# TI.net
KiCad netlist of a schematic drawn in EasyEDA Pro
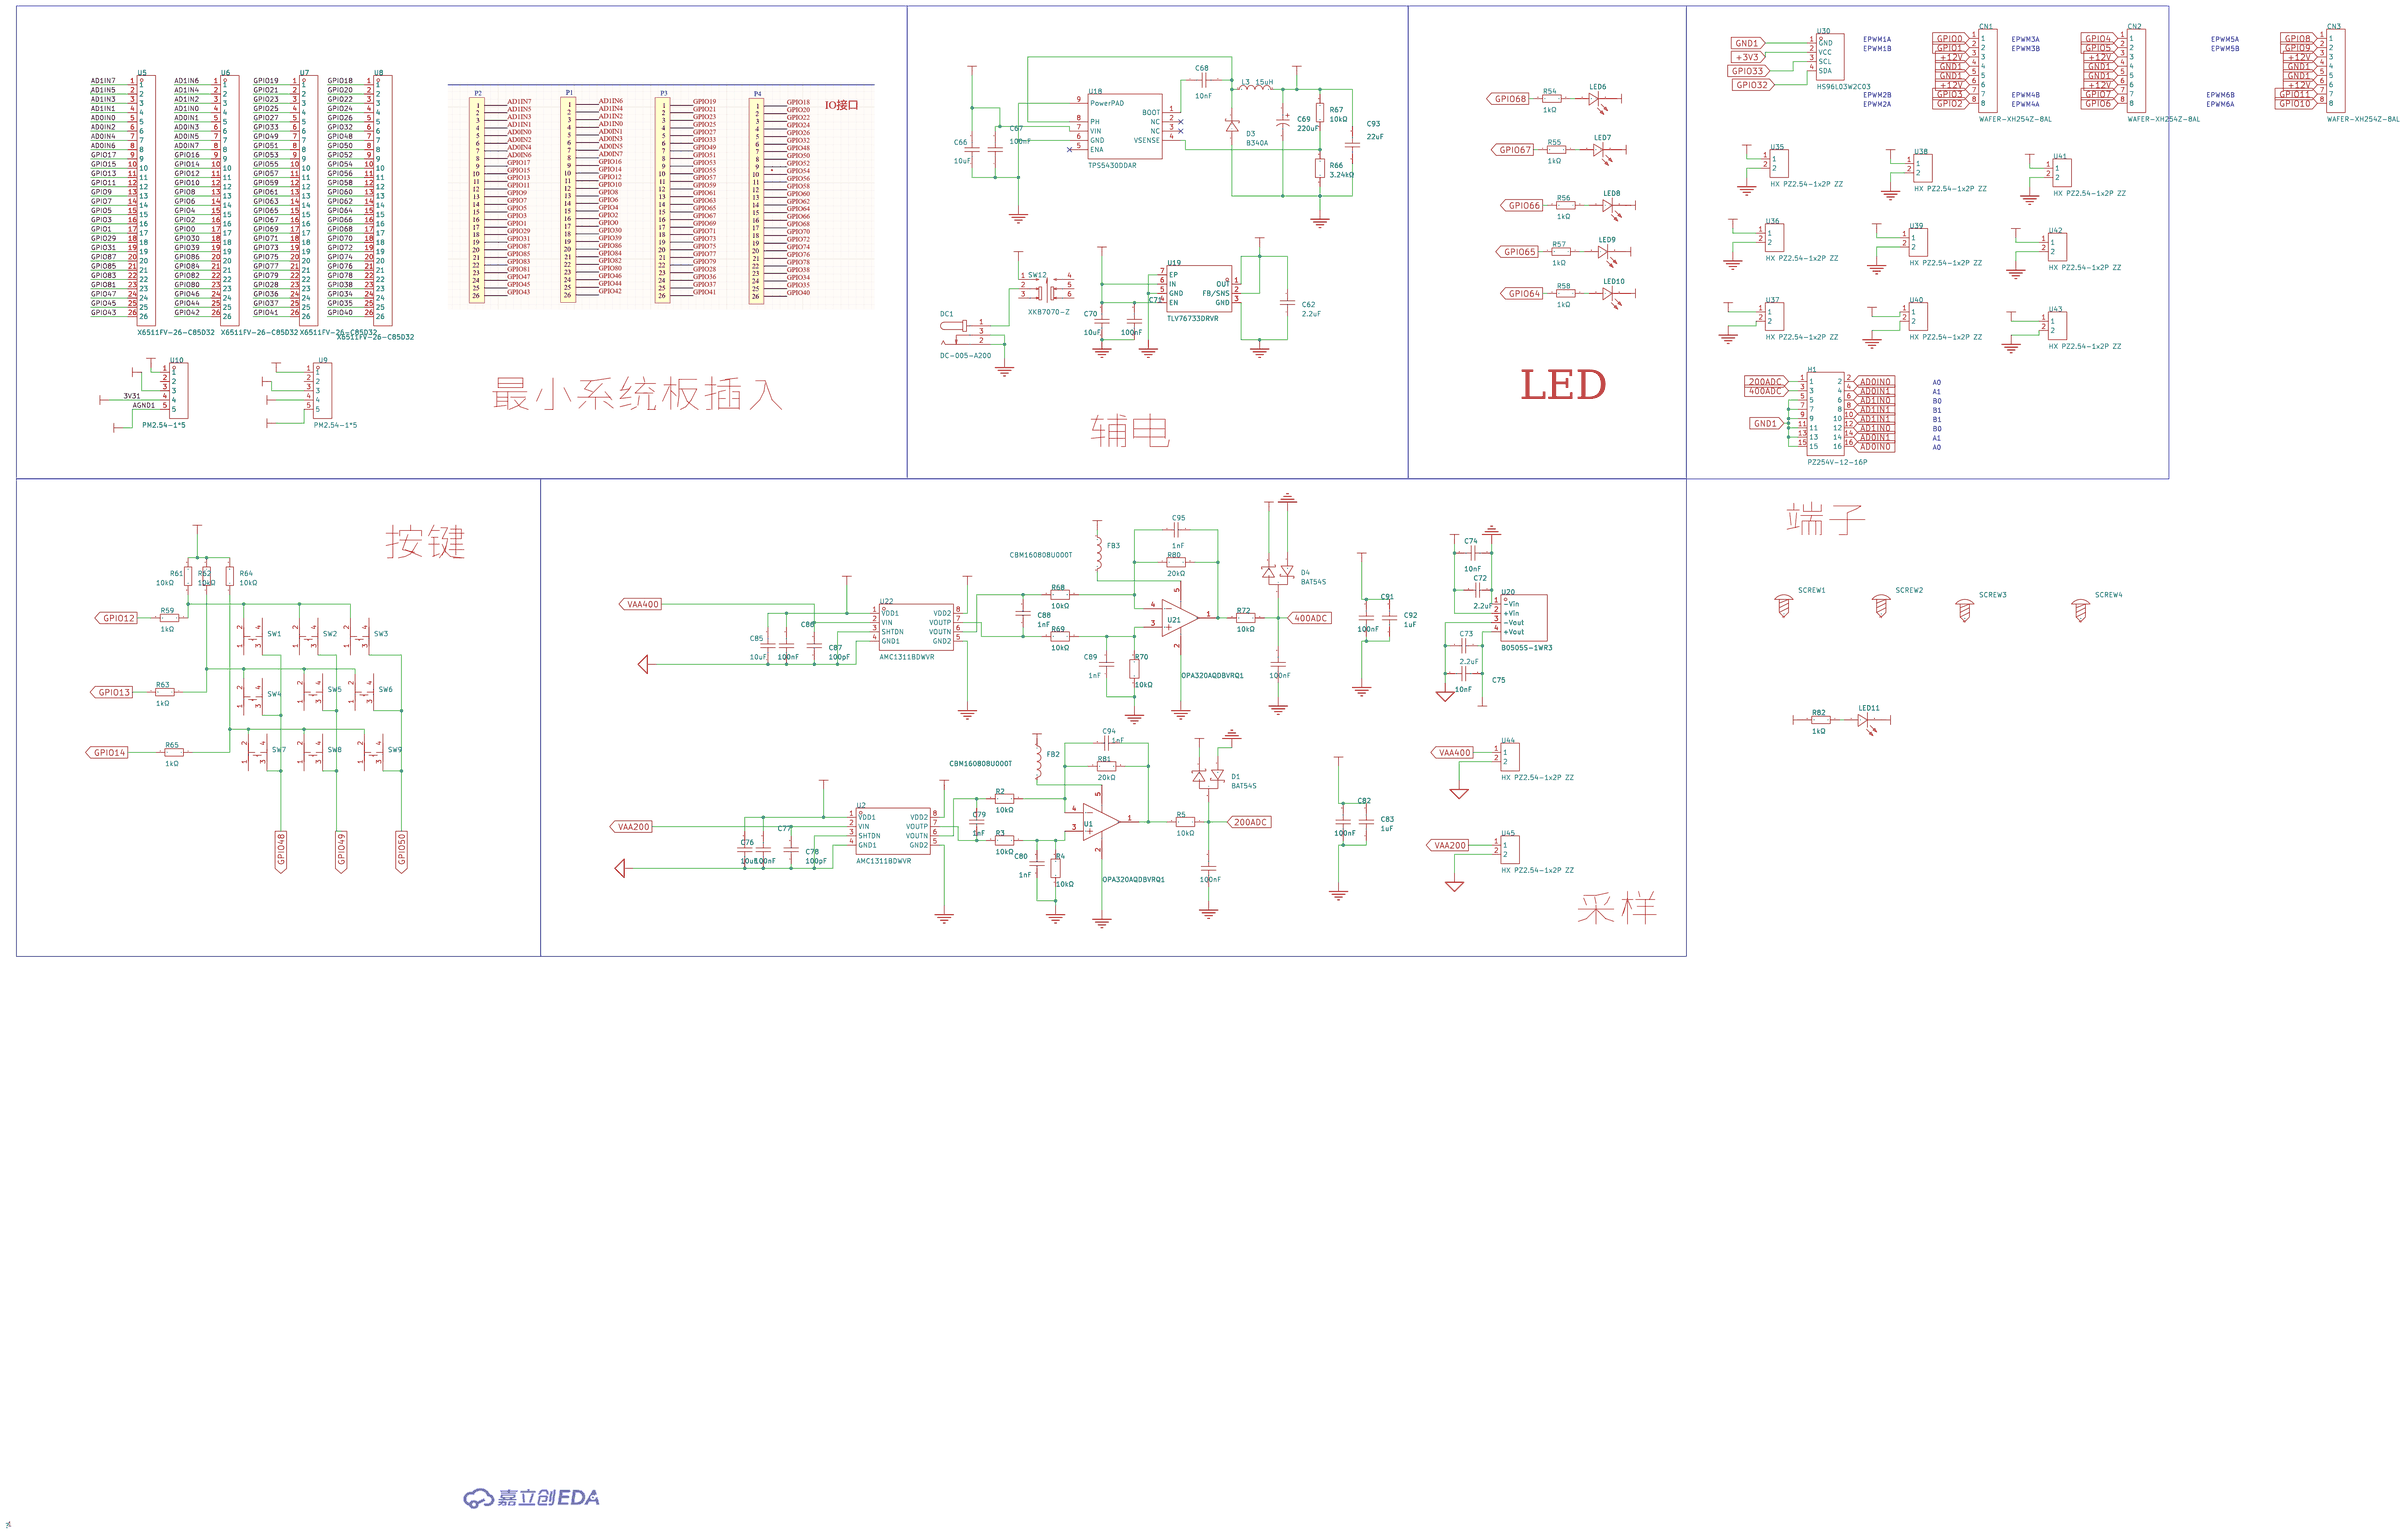
[diagram p0: schematic sheet]

(export (version "E")
  (design (tool "Eeschema 10.0.6"))
  (components
    (comp (ref "C62")
      (value "2.2uF")
      (footprint "easyedapro:C0603")
      (description "容值:2.2uF;精度:±10%;额定电压:16V;材质(温度系数):X5R;")
      (fields
        (field (name "Manufacturer Part") "CL10A225KO8NNNC")
        (field (name "Manufacturer") "SAMSUNG(三星)")
      )
      (libsource (lib "easyedapro") (part "CL10A225KO8NNNC"))
    )
    (comp (ref "C66")
      (value "10uF")
      (footprint "easyedapro:C0603")
      (description "容值:10uF;精度:±10%;额定电压:16V;温度系数:X5R;")
      (fields
        (field (name "Manufacturer Part") "CL10A106KO8NQNC")
        (field (name "Manufacturer") "SAMSUNG(三星)")
      )
      (libsource (lib "easyedapro") (part "CL10A106KO8NQNC"))
    )
    (comp (ref "C67")
      (value "100nF")
      (footprint "easyedapro:C0603")
      (description "容值:100nF;精度:±10%;额定电压:16V;温度系数:X7R;")
      (fields
        (field (name "Manufacturer Part") "CC0603KRX7R7BB104")
        (field (name "Manufacturer") "YAGEO(国巨)")
      )
      (libsource (lib "easyedapro") (part "CC0603KRX7R7BB104"))
    )
    (comp (ref "C68")
      (value "10nF")
      (footprint "easyedapro:C0603")
      (description "容值:10nF;精度:±10%;额定电压:16V;温度系数:X7R;")
      (fields
        (field (name "Manufacturer Part") "CC0603KRX7R7BB103")
        (field (name "Manufacturer") "YAGEO(国巨)")
      )
      (libsource (lib "easyedapro") (part "CC0603KRX7R7BB103"))
    )
    (comp (ref "C69")
      (value "220uF")
      (footprint "easyedapro:CAP-SMD_BD6.3-L6.6-W6.6-FD")
      (description "容值:220uF;精度:±20%;额定电压:16V;纹波电流:95mA@120Hz;等效串联电阻(ESR):-;")
      (fields
        (field (name "Manufacturer Part") "RST220UF16V167RV0019")
        (field (name "Manufacturer") "KNSCHA(科尼盛)")
      )
      (libsource (lib "easyedapro") (part "RST220UF16V167RV0019"))
    )
    (comp (ref "C70")
      (value "10uF")
      (footprint "easyedapro:C0603")
      (description "容值:10uF;精度:±10%;额定电压:16V;温度系数:X5R;")
      (fields
        (field (name "Manufacturer Part") "CL10A106KO8NQNC")
        (field (name "Manufacturer") "SAMSUNG(三星)")
      )
      (libsource (lib "easyedapro") (part "CL10A106KO8NQNC"))
    )
    (comp (ref "C71")
      (value "100nF")
      (footprint "easyedapro:C0603")
      (description "容值:100nF;精度:±10%;额定电压:16V;温度系数:X7R;")
      (fields
        (field (name "Manufacturer Part") "CC0603KRX7R7BB104")
        (field (name "Manufacturer") "YAGEO(国巨)")
      )
      (libsource (lib "easyedapro") (part "CC0603KRX7R7BB104"))
    )
    (comp (ref "C72")
      (value "2.2uF")
      (footprint "easyedapro:C0603")
      (description "容值:2.2uF;精度:±10%;额定电压:16V;材质(温度系数):X5R;")
      (fields
        (field (name "Manufacturer Part") "CL10A225KO8NNNC")
        (field (name "Manufacturer") "SAMSUNG(三星)")
      )
      (libsource (lib "easyedapro") (part "CL10A225KO8NNNC"))
    )
    (comp (ref "C73")
      (value "2.2uF")
      (footprint "easyedapro:C0603")
      (description "容值:2.2uF;精度:±10%;额定电压:16V;材质(温度系数):X5R;")
      (fields
        (field (name "Manufacturer Part") "CL10A225KO8NNNC")
        (field (name "Manufacturer") "SAMSUNG(三星)")
      )
      (libsource (lib "easyedapro") (part "CL10A225KO8NNNC"))
    )
    (comp (ref "C74")
      (value "10nF")
      (footprint "easyedapro:C0603")
      (description "容值:10nF;精度:±10%;额定电压:16V;温度系数:X7R;")
      (fields
        (field (name "Manufacturer Part") "CC0603KRX7R7BB103")
        (field (name "Manufacturer") "YAGEO(国巨)")
      )
      (libsource (lib "easyedapro") (part "CC0603KRX7R7BB103"))
    )
    (comp (ref "C75")
      (value "10nF")
      (footprint "easyedapro:C0603")
      (description "容值:10nF;精度:±10%;额定电压:16V;温度系数:X7R;")
      (fields
        (field (name "Manufacturer Part") "CC0603KRX7R7BB103")
        (field (name "Manufacturer") "YAGEO(国巨)")
      )
      (libsource (lib "easyedapro") (part "CC0603KRX7R7BB103"))
    )
    (comp (ref "C76")
      (value "10uF")
      (footprint "easyedapro:C0603")
      (description "容值:10uF;精度:±10%;额定电压:16V;温度系数:X5R;")
      (fields
        (field (name "Manufacturer Part") "CL10A106KO8NQNC")
        (field (name "Manufacturer") "SAMSUNG(三星)")
      )
      (libsource (lib "easyedapro") (part "CL10A106KO8NQNC"))
    )
    (comp (ref "C77")
      (value "100nF")
      (footprint "easyedapro:C0603")
      (description "容值:100nF;精度:±10%;额定电压:16V;温度系数:X7R;")
      (fields
        (field (name "Manufacturer Part") "CC0603KRX7R7BB104")
        (field (name "Manufacturer") "YAGEO(国巨)")
      )
      (libsource (lib "easyedapro") (part "CC0603KRX7R7BB104"))
    )
    (comp (ref "C78")
      (value "100pF")
      (footprint "easyedapro:C0603")
      (description "容值:100pF;精度:±10%;额定电压:50V;温度系数:X7R;")
      (fields
        (field (name "Manufacturer Part") "CC0603KRX7R9BB101")
        (field (name "Manufacturer") "YAGEO(国巨)")
      )
      (libsource (lib "easyedapro") (part "CC0603KRX7R9BB101"))
    )
    (comp (ref "C79")
      (value "1nF")
      (footprint "easyedapro:C0603")
      (description "容值:1nF;精度:±10%;额定电压:50V;温度系数:X7R;")
      (fields
        (field (name "Manufacturer Part") "CL10B102KB8NNNC")
        (field (name "Manufacturer") "SAMSUNG(三星)")
      )
      (libsource (lib "easyedapro") (part "CL10B102KB8NNNC"))
    )
    (comp (ref "C80")
      (value "1nF")
      (footprint "easyedapro:C0603")
      (description "容值:1nF;精度:±10%;额定电压:50V;温度系数:X7R;")
      (fields
        (field (name "Manufacturer Part") "CL10B102KB8NNNC")
        (field (name "Manufacturer") "SAMSUNG(三星)")
      )
      (libsource (lib "easyedapro") (part "CL10B102KB8NNNC"))
    )
    (comp (ref "C81")
      (value "100nF")
      (footprint "easyedapro:C0603")
      (description "容值:100nF;精度:±10%;额定电压:16V;温度系数:X7R;")
      (fields
        (field (name "Manufacturer Part") "CC0603KRX7R7BB104")
        (field (name "Manufacturer") "YAGEO(国巨)")
      )
      (libsource (lib "easyedapro") (part "CC0603KRX7R7BB104"))
    )
    (comp (ref "C82")
      (value "100nF")
      (footprint "easyedapro:C0603")
      (description "容值:100nF;精度:±10%;额定电压:16V;温度系数:X7R;")
      (fields
        (field (name "Manufacturer Part") "CC0603KRX7R7BB104")
        (field (name "Manufacturer") "YAGEO(国巨)")
      )
      (libsource (lib "easyedapro") (part "CC0603KRX7R7BB104"))
    )
    (comp (ref "C83")
      (value "1uF")
      (footprint "easyedapro:C0603")
      (description "容值:1uF;精度:±10%;额定电压:50V;温度系数:X5R;")
      (fields
        (field (name "Manufacturer Part") "CL10A105KB8NNNC")
        (field (name "Manufacturer") "SAMSUNG(三星)")
      )
      (libsource (lib "easyedapro") (part "CL10A105KB8NNNC"))
    )
    (comp (ref "C85")
      (value "10uF")
      (footprint "easyedapro:C0603")
      (description "容值:10uF;精度:±10%;额定电压:16V;温度系数:X5R;")
      (fields
        (field (name "Manufacturer Part") "CL10A106KO8NQNC")
        (field (name "Manufacturer") "SAMSUNG(三星)")
      )
      (libsource (lib "easyedapro") (part "CL10A106KO8NQNC"))
    )
    (comp (ref "C86")
      (value "100nF")
      (footprint "easyedapro:C0603")
      (description "容值:100nF;精度:±10%;额定电压:16V;温度系数:X7R;")
      (fields
        (field (name "Manufacturer Part") "CC0603KRX7R7BB104")
        (field (name "Manufacturer") "YAGEO(国巨)")
      )
      (libsource (lib "easyedapro") (part "CC0603KRX7R7BB104"))
    )
    (comp (ref "C87")
      (value "100pF")
      (footprint "easyedapro:C0603")
      (description "容值:100pF;精度:±10%;额定电压:50V;温度系数:X7R;")
      (fields
        (field (name "Manufacturer Part") "CC0603KRX7R9BB101")
        (field (name "Manufacturer") "YAGEO(国巨)")
      )
      (libsource (lib "easyedapro") (part "CC0603KRX7R9BB101"))
    )
    (comp (ref "C88")
      (value "1nF")
      (footprint "easyedapro:C0603")
      (description "容值:1nF;精度:±10%;额定电压:50V;温度系数:X7R;")
      (fields
        (field (name "Manufacturer Part") "CL10B102KB8NNNC")
        (field (name "Manufacturer") "SAMSUNG(三星)")
      )
      (libsource (lib "easyedapro") (part "CL10B102KB8NNNC"))
    )
    (comp (ref "C89")
      (value "1nF")
      (footprint "easyedapro:C0603")
      (description "容值:1nF;精度:±10%;额定电压:50V;温度系数:X7R;")
      (fields
        (field (name "Manufacturer Part") "CL10B102KB8NNNC")
        (field (name "Manufacturer") "SAMSUNG(三星)")
      )
      (libsource (lib "easyedapro") (part "CL10B102KB8NNNC"))
    )
    (comp (ref "C90")
      (value "100nF")
      (footprint "easyedapro:C0603")
      (description "容值:100nF;精度:±10%;额定电压:16V;温度系数:X7R;")
      (fields
        (field (name "Manufacturer Part") "CC0603KRX7R7BB104")
        (field (name "Manufacturer") "YAGEO(国巨)")
      )
      (libsource (lib "easyedapro") (part "CC0603KRX7R7BB104"))
    )
    (comp (ref "C91")
      (value "100nF")
      (footprint "easyedapro:C0603")
      (description "容值:100nF;精度:±10%;额定电压:16V;温度系数:X7R;")
      (fields
        (field (name "Manufacturer Part") "CC0603KRX7R7BB104")
        (field (name "Manufacturer") "YAGEO(国巨)")
      )
      (libsource (lib "easyedapro") (part "CC0603KRX7R7BB104"))
    )
    (comp (ref "C92")
      (value "1uF")
      (footprint "easyedapro:C0603")
      (description "容值:1uF;精度:±10%;额定电压:50V;温度系数:X5R;")
      (fields
        (field (name "Manufacturer Part") "CL10A105KB8NNNC")
        (field (name "Manufacturer") "SAMSUNG(三星)")
      )
      (libsource (lib "easyedapro") (part "CL10A105KB8NNNC"))
    )
    (comp (ref "C93")
      (value "22uF")
      (footprint "easyedapro:C0805")
      (description "容值:22uF;精度:±10%;额定电压:16V;温度系数:X5R;")
      (fields
        (field (name "Manufacturer Part") "CL21A226KOQNNNE")
        (field (name "Manufacturer") "SAMSUNG(三星)")
      )
      (libsource (lib "easyedapro") (part "CL21A226KOQNNNE"))
    )
    (comp (ref "C94")
      (value "1nF")
      (footprint "easyedapro:C0603")
      (description "容值:1nF;精度:±10%;额定电压:50V;温度系数:X7R;")
      (fields
        (field (name "Manufacturer Part") "CL10B102KB8NNNC")
        (field (name "Manufacturer") "SAMSUNG(三星)")
      )
      (libsource (lib "easyedapro") (part "CL10B102KB8NNNC"))
    )
    (comp (ref "C95")
      (value "1nF")
      (footprint "easyedapro:C0603")
      (description "容值:1nF;精度:±10%;额定电压:50V;温度系数:X7R;")
      (fields
        (field (name "Manufacturer Part") "CL10B102KB8NNNC")
        (field (name "Manufacturer") "SAMSUNG(三星)")
      )
      (libsource (lib "easyedapro") (part "CL10B102KB8NNNC"))
    )
    (comp (ref "CN1")
      (value "WAFER-XH254Z-8AL")
      (footprint "easyedapro:CONN-TH_WAFER-XH254Z-8A")
      (description "插针结构:1x8P;间距:2.54mm;安装方式:直插;参考系列:XH;总PIN数:8P;排数:1;每排PIN数:8;额定电流:3A;触头材质:黄铜;工作温度:-25°C~+85°C;")
      (fields (field (name "Manufacturer") "HANBO(汉博)"))
      (libsource (lib "easyedapro") (part "WAFER-XH254Z-8AL"))
    )
    (comp (ref "CN2")
      (value "WAFER-XH254Z-8AL")
      (footprint "easyedapro:CONN-TH_WAFER-XH254Z-8A")
      (description "插针结构:1x8P;间距:2.54mm;安装方式:直插;参考系列:XH;总PIN数:8P;排数:1;每排PIN数:8;额定电流:3A;触头材质:黄铜;工作温度:-25°C~+85°C;")
      (fields (field (name "Manufacturer") "HANBO(汉博)"))
      (libsource (lib "easyedapro") (part "WAFER-XH254Z-8AL"))
    )
    (comp (ref "CN3")
      (value "WAFER-XH254Z-8AL")
      (footprint "easyedapro:CONN-TH_WAFER-XH254Z-8A")
      (description "插针结构:1x8P;间距:2.54mm;安装方式:直插;参考系列:XH;总PIN数:8P;排数:1;每排PIN数:8;额定电流:3A;触头材质:黄铜;工作温度:-25°C~+85°C;")
      (fields (field (name "Manufacturer") "HANBO(汉博)"))
      (libsource (lib "easyedapro") (part "WAFER-XH254Z-8AL"))
    )
    (comp (ref "D1")
      (value "BAT54S")
      (footprint "easyedapro:SOT-23-3_L2.9-W1.3-P1.90-LS2.4-BR")
      (description "二极管配置:1对串联式;正向压降(Vf):400mV@10mA;直流反向耐压(Vr):30V;整流电流:200mA;")
      (fields (field (name "Manufacturer") "宏嘉诚"))
      (libsource (lib "easyedapro") (part "BAT54S_C7420333"))
    )
    (comp (ref "D3")
      (value "B340A")
      (footprint "easyedapro:SMA_L4.3-W2.6-LS5.1-RD")
      (description "二极管配置:独立式;正向压降(Vf):550mV@3A;直流反向耐压(Vr):40V;整流电流:3A;")
      (fields (field (name "Manufacturer") "MDD(辰达半导体)"))
      (libsource (lib "easyedapro") (part "B340A"))
    )
    (comp (ref "D4")
      (value "BAT54S")
      (footprint "easyedapro:SOT-23-3_L2.9-W1.3-P1.90-LS2.4-BR")
      (description "二极管配置:1对串联式;正向压降(Vf):400mV@10mA;直流反向耐压(Vr):30V;整流电流:200mA;")
      (fields (field (name "Manufacturer") "宏嘉诚"))
      (libsource (lib "easyedapro") (part "BAT54S_C7420333"))
    )
    (comp (ref "DC1")
      (value "DC-005-A200")
      (footprint "easyedapro:DC-IN-TH_DC-005-A200")
      (description "连接器类型:DC电源插座;安装方式:弯插;触点内径:2mm;触点外径:6.4mm;额定电流:3A;额定电压:30V;工作温度:-20°C~+70°C;")
      (fields (field (name "Manufacturer") "XUNPU(讯普)"))
      (libsource (lib "easyedapro") (part "DC-005-A200"))
    )
    (comp (ref "FB2")
      (value "CBM160808U000T")
      (footprint "easyedapro:L0603")
      (description "阻抗@频率:0Ω@100MHz;直流电阻(DCR):10mΩ;")
      (fields (field (name "Manufacturer") "FH(风华)"))
      (libsource (lib "easyedapro") (part "CBM160808U000T"))
    )
    (comp (ref "FB3")
      (value "CBM160808U000T")
      (footprint "easyedapro:L0603")
      (description "阻抗@频率:0Ω@100MHz;直流电阻(DCR):10mΩ;")
      (fields (field (name "Manufacturer") "FH(风华)"))
      (libsource (lib "easyedapro") (part "CBM160808U000T"))
    )
    (comp (ref "H1")
      (value "PZ254V-12-16P")
      (footprint "easyedapro:HDR-TH_16P-P2.54-V-M-R2-C8-S2.54")
      (fields (field (name "Manufacturer") "XFCN(兴飞)"))
      (libsource (lib "easyedapro") (part "PZ254V-12-16P"))
    )
    (comp (ref "L3")
      (value "15uH")
      (footprint "easyedapro:IND-SMD_L7.3-W6.8")
      (description "精度:±20%;额定电流:3A;电感值:15uH;直流电阻(DCR):113mΩ;")
      (fields
        (field (name "Manufacturer Part") "MWSA0603S-150MT")
        (field (name "Manufacturer") "Sunlord(顺络)")
      )
      (libsource (lib "easyedapro") (part "MWSA0603S-150MT"))
    )
    (comp (ref "LED6")
      (value "NCD0805R1")
      (footprint "easyedapro:LED0805-R-RD")
      (fields (field (name "Manufacturer") "国星光电"))
      (libsource (lib "easyedapro") (part "FC-2012HRK-620D"))
    )
    (comp (ref "LED7")
      (value "NCD0805R1")
      (footprint "easyedapro:LED0805-R-RD")
      (fields (field (name "Manufacturer") "国星光电"))
      (libsource (lib "easyedapro") (part "FC-2012HRK-620D"))
    )
    (comp (ref "LED8")
      (value "NCD0805R1")
      (footprint "easyedapro:LED0805-R-RD")
      (fields (field (name "Manufacturer") "国星光电"))
      (libsource (lib "easyedapro") (part "FC-2012HRK-620D"))
    )
    (comp (ref "LED9")
      (value "NCD0805R1")
      (footprint "easyedapro:LED0805-R-RD")
      (fields (field (name "Manufacturer") "国星光电"))
      (libsource (lib "easyedapro") (part "FC-2012HRK-620D"))
    )
    (comp (ref "LED10")
      (value "NCD0805R1")
      (footprint "easyedapro:LED0805-R-RD")
      (fields (field (name "Manufacturer") "国星光电"))
      (libsource (lib "easyedapro") (part "FC-2012HRK-620D"))
    )
    (comp (ref "LED11")
      (value "NCD0805R1")
      (footprint "easyedapro:LED0805-R-RD")
      (fields (field (name "Manufacturer") "国星光电"))
      (libsource (lib "easyedapro") (part "FC-2012HRK-620D"))
    )
    (comp (ref "R2")
      (value "10kΩ")
      (footprint "easyedapro:R0603")
      (description "电阻类型:薄膜电阻;阻值:4.7Ω;精度:±0.1%;功率:100mW;温度系数:±25ppm/°C;")
      (fields (field (name "Manufacturer Part") "RT0603BRD074R7L") (field (name "Manufacturer") "YAGEO(国巨)"))
      (libsource (lib "easyedapro") (part "RT0603BRD074R7L"))
    )
    (comp (ref "R3")
      (value "10kΩ")
      (footprint "easyedapro:R0603")
      (description "电阻类型:薄膜电阻;阻值:4.7Ω;精度:±0.1%;功率:100mW;温度系数:±25ppm/°C;")
      (fields (field (name "Manufacturer Part") "RT0603BRD074R7L") (field (name "Manufacturer") "YAGEO(国巨)"))
      (libsource (lib "easyedapro") (part "RT0603BRD074R7L"))
    )
    (comp (ref "R4")
      (value "10kΩ")
      (footprint "easyedapro:R0603")
      (description "电阻类型:薄膜电阻;阻值:4.7Ω;精度:±0.1%;功率:100mW;温度系数:±25ppm/°C;")
      (fields (field (name "Manufacturer Part") "RT0603BRD074R7L") (field (name "Manufacturer") "YAGEO(国巨)"))
      (libsource (lib "easyedapro") (part "RT0603BRD074R7L"))
    )
    (comp (ref "R5")
      (value "10kΩ")
      (footprint "easyedapro:R0603")
      (description "电阻类型:薄膜电阻;阻值:4.7Ω;精度:±0.1%;功率:100mW;温度系数:±25ppm/°C;")
      (fields (field (name "Manufacturer Part") "RT0603BRD074R7L") (field (name "Manufacturer") "YAGEO(国巨)"))
      (libsource (lib "easyedapro") (part "RT0603BRD074R7L"))
    )
    (comp (ref "R54")
      (value "1kΩ")
      (footprint "easyedapro:R0603")
      (description "电阻类型:厚膜电阻;阻值:1kΩ;精度:±1%;功率:100mW;最大工作电压:75V;温度系数:±100ppm/°C;")
      (fields
        (field (name "Manufacturer Part") "0603WAF1001T5E")
        (field (name "Manufacturer") "UNI-ROYAL(厚声)")
      )
      (libsource (lib "easyedapro") (part "0603WAF1001T5E"))
    )
    (comp (ref "R55")
      (value "1kΩ")
      (footprint "easyedapro:R0603")
      (description "电阻类型:厚膜电阻;阻值:1kΩ;精度:±1%;功率:100mW;最大工作电压:75V;温度系数:±100ppm/°C;")
      (fields
        (field (name "Manufacturer Part") "0603WAF1001T5E")
        (field (name "Manufacturer") "UNI-ROYAL(厚声)")
      )
      (libsource (lib "easyedapro") (part "0603WAF1001T5E"))
    )
    (comp (ref "R56")
      (value "1kΩ")
      (footprint "easyedapro:R0603")
      (description "电阻类型:厚膜电阻;阻值:1kΩ;精度:±1%;功率:100mW;最大工作电压:75V;温度系数:±100ppm/°C;")
      (fields
        (field (name "Manufacturer Part") "0603WAF1001T5E")
        (field (name "Manufacturer") "UNI-ROYAL(厚声)")
      )
      (libsource (lib "easyedapro") (part "0603WAF1001T5E"))
    )
    (comp (ref "R57")
      (value "1kΩ")
      (footprint "easyedapro:R0603")
      (description "电阻类型:厚膜电阻;阻值:1kΩ;精度:±1%;功率:100mW;最大工作电压:75V;温度系数:±100ppm/°C;")
      (fields
        (field (name "Manufacturer Part") "0603WAF1001T5E")
        (field (name "Manufacturer") "UNI-ROYAL(厚声)")
      )
      (libsource (lib "easyedapro") (part "0603WAF1001T5E"))
    )
    (comp (ref "R58")
      (value "1kΩ")
      (footprint "easyedapro:R0603")
      (description "电阻类型:厚膜电阻;阻值:1kΩ;精度:±1%;功率:100mW;最大工作电压:75V;温度系数:±100ppm/°C;")
      (fields
        (field (name "Manufacturer Part") "0603WAF1001T5E")
        (field (name "Manufacturer") "UNI-ROYAL(厚声)")
      )
      (libsource (lib "easyedapro") (part "0603WAF1001T5E"))
    )
    (comp (ref "R59")
      (value "1kΩ")
      (footprint "easyedapro:R0603")
      (description "电阻类型:厚膜电阻;阻值:1kΩ;精度:±1%;功率:100mW;最大工作电压:75V;温度系数:±100ppm/°C;")
      (fields
        (field (name "Manufacturer Part") "0603WAF1001T5E")
        (field (name "Manufacturer") "UNI-ROYAL(厚声)")
      )
      (libsource (lib "easyedapro") (part "0603WAF1001T5E"))
    )
    (comp (ref "R61")
      (value "10kΩ")
      (footprint "easyedapro:R0603")
      (description "电阻类型:厚膜电阻;阻值:10kΩ;精度:±1%;功率:100mW;工作电压:75V;温度系数:±100ppm/°C;")
      (fields
        (field (name "Manufacturer Part") "0603WAF1002T5E")
        (field (name "Manufacturer") "UNI-ROYAL(厚声)")
      )
      (libsource (lib "easyedapro") (part "0603WAF1002T5E"))
    )
    (comp (ref "R62")
      (value "10kΩ")
      (footprint "easyedapro:R0603")
      (description "电阻类型:厚膜电阻;阻值:10kΩ;精度:±1%;功率:100mW;工作电压:75V;温度系数:±100ppm/°C;")
      (fields
        (field (name "Manufacturer Part") "0603WAF1002T5E")
        (field (name "Manufacturer") "UNI-ROYAL(厚声)")
      )
      (libsource (lib "easyedapro") (part "0603WAF1002T5E"))
    )
    (comp (ref "R63")
      (value "1kΩ")
      (footprint "easyedapro:R0603")
      (description "电阻类型:厚膜电阻;阻值:1kΩ;精度:±1%;功率:100mW;最大工作电压:75V;温度系数:±100ppm/°C;")
      (fields
        (field (name "Manufacturer Part") "0603WAF1001T5E")
        (field (name "Manufacturer") "UNI-ROYAL(厚声)")
      )
      (libsource (lib "easyedapro") (part "0603WAF1001T5E"))
    )
    (comp (ref "R64")
      (value "10kΩ")
      (footprint "easyedapro:R0603")
      (description "电阻类型:厚膜电阻;阻值:10kΩ;精度:±1%;功率:100mW;工作电压:75V;温度系数:±100ppm/°C;")
      (fields
        (field (name "Manufacturer Part") "0603WAF1002T5E")
        (field (name "Manufacturer") "UNI-ROYAL(厚声)")
      )
      (libsource (lib "easyedapro") (part "0603WAF1002T5E"))
    )
    (comp (ref "R65")
      (value "1kΩ")
      (footprint "easyedapro:R0603")
      (description "电阻类型:厚膜电阻;阻值:1kΩ;精度:±1%;功率:100mW;最大工作电压:75V;温度系数:±100ppm/°C;")
      (fields
        (field (name "Manufacturer Part") "0603WAF1001T5E")
        (field (name "Manufacturer") "UNI-ROYAL(厚声)")
      )
      (libsource (lib "easyedapro") (part "0603WAF1001T5E"))
    )
    (comp (ref "R66")
      (value "3.24kΩ")
      (footprint "easyedapro:R0603")
      (description "电阻类型:薄膜电阻;阻值:3.24kΩ;精度:±0.1%;功率:100mW;温度系数:±25ppm/°C;")
      (fields (field (name "Manufacturer Part") "RT0603BRD073K24L") (field (name "Manufacturer") "YAGEO(国巨)"))
      (libsource (lib "easyedapro") (part "RT0603BRD073K24L"))
    )
    (comp (ref "R67")
      (value "10kΩ")
      (footprint "easyedapro:R0603")
      (description "电阻类型:厚膜电阻;阻值:10kΩ;精度:±1%;功率:100mW;工作电压:75V;温度系数:±100ppm/°C;")
      (fields
        (field (name "Manufacturer Part") "0603WAF1002T5E")
        (field (name "Manufacturer") "UNI-ROYAL(厚声)")
      )
      (libsource (lib "easyedapro") (part "0603WAF1002T5E"))
    )
    (comp (ref "R68")
      (value "10kΩ")
      (footprint "easyedapro:R0603")
      (description "电阻类型:薄膜电阻;阻值:4.7Ω;精度:±0.1%;功率:100mW;温度系数:±25ppm/°C;")
      (fields (field (name "Manufacturer Part") "RT0603BRD074R7L") (field (name "Manufacturer") "YAGEO(国巨)"))
      (libsource (lib "easyedapro") (part "RT0603BRD074R7L"))
    )
    (comp (ref "R69")
      (value "10kΩ")
      (footprint "easyedapro:R0603")
      (description "电阻类型:薄膜电阻;阻值:4.7Ω;精度:±0.1%;功率:100mW;温度系数:±25ppm/°C;")
      (fields (field (name "Manufacturer Part") "RT0603BRD074R7L") (field (name "Manufacturer") "YAGEO(国巨)"))
      (libsource (lib "easyedapro") (part "RT0603BRD074R7L"))
    )
    (comp (ref "R70")
      (value "10kΩ")
      (footprint "easyedapro:R0603")
      (description "电阻类型:薄膜电阻;阻值:4.7Ω;精度:±0.1%;功率:100mW;温度系数:±25ppm/°C;")
      (fields (field (name "Manufacturer Part") "RT0603BRD074R7L") (field (name "Manufacturer") "YAGEO(国巨)"))
      (libsource (lib "easyedapro") (part "RT0603BRD074R7L"))
    )
    (comp (ref "R72")
      (value "10kΩ")
      (footprint "easyedapro:R0603")
      (description "电阻类型:薄膜电阻;阻值:4.7Ω;精度:±0.1%;功率:100mW;温度系数:±25ppm/°C;")
      (fields (field (name "Manufacturer Part") "RT0603BRD074R7L") (field (name "Manufacturer") "YAGEO(国巨)"))
      (libsource (lib "easyedapro") (part "RT0603BRD074R7L"))
    )
    (comp (ref "R80")
      (value "20kΩ")
      (footprint "easyedapro:R0603")
      (description "电阻类型:薄膜电阻;阻值:20kΩ;精度:±0.1%;功率:100mW;工作电压:75V;温度系数:±25ppm/°C;")
      (fields (field (name "Manufacturer Part") "RT0603BRD0720KL") (field (name "Manufacturer") "YAGEO(国巨)"))
      (libsource (lib "easyedapro") (part "RT0603BRD0720KL"))
    )
    (comp (ref "R81")
      (value "20kΩ")
      (footprint "easyedapro:R0603")
      (description "电阻类型:薄膜电阻;阻值:20kΩ;精度:±0.1%;功率:100mW;工作电压:75V;温度系数:±25ppm/°C;")
      (fields (field (name "Manufacturer Part") "RT0603BRD0720KL") (field (name "Manufacturer") "YAGEO(国巨)"))
      (libsource (lib "easyedapro") (part "RT0603BRD0720KL"))
    )
    (comp (ref "R82")
      (value "1kΩ")
      (footprint "easyedapro:R0603")
      (description "电阻类型:厚膜电阻;阻值:1kΩ;精度:±1%;功率:100mW;最大工作电压:75V;温度系数:±100ppm/°C;")
      (fields
        (field (name "Manufacturer Part") "0603WAF1001T5E")
        (field (name "Manufacturer") "UNI-ROYAL(厚声)")
      )
      (libsource (lib "easyedapro") (part "0603WAF1001T5E"))
    )
    (comp (ref "SCREW1")
      (value "~")
      (footprint "easyedapro:M4螺丝")
      (libsource (lib "easyedapro") (part "螺丝孔"))
    )
    (comp (ref "SCREW2")
      (value "~")
      (footprint "easyedapro:M4螺丝")
      (libsource (lib "easyedapro") (part "螺丝孔"))
    )
    (comp (ref "SCREW3")
      (value "~")
      (footprint "easyedapro:M4螺丝")
      (libsource (lib "easyedapro") (part "螺丝孔"))
    )
    (comp (ref "SCREW4")
      (value "~")
      (footprint "easyedapro:M4螺丝")
      (libsource (lib "easyedapro") (part "螺丝孔"))
    )
    (comp (ref "SW1")
      (value "TS-1095-A10B3-D1")
      (footprint "easyedapro:SW-TH_4P-L6.0-W6.0-P4.50-LS6.5")
      (description "电路结构:单刀单掷;按钮形状:圆形按钮;作用力:2.5N;安装方式:-;开关长度:6mm;开关宽度:6mm;开关高度:8.5mm;带灯:-;工作寿命:-;")
      (fields (field (name "Manufacturer") "Yuandi(元迪)"))
      (libsource (lib "easyedapro") (part "TS-1095-A10B3-D1"))
    )
    (comp (ref "SW2")
      (value "TS-1095-A10B3-D1")
      (footprint "easyedapro:SW-TH_4P-L6.0-W6.0-P4.50-LS6.5")
      (description "电路结构:单刀单掷;按钮形状:圆形按钮;作用力:2.5N;安装方式:-;开关长度:6mm;开关宽度:6mm;开关高度:8.5mm;带灯:-;工作寿命:-;")
      (fields (field (name "Manufacturer") "Yuandi(元迪)"))
      (libsource (lib "easyedapro") (part "TS-1095-A10B3-D1"))
    )
    (comp (ref "SW3")
      (value "TS-1095-A10B3-D1")
      (footprint "easyedapro:SW-TH_4P-L6.0-W6.0-P4.50-LS6.5")
      (description "电路结构:单刀单掷;按钮形状:圆形按钮;作用力:2.5N;安装方式:-;开关长度:6mm;开关宽度:6mm;开关高度:8.5mm;带灯:-;工作寿命:-;")
      (fields (field (name "Manufacturer") "Yuandi(元迪)"))
      (libsource (lib "easyedapro") (part "TS-1095-A10B3-D1"))
    )
    (comp (ref "SW4")
      (value "TS-1095-A10B3-D1")
      (footprint "easyedapro:SW-TH_4P-L6.0-W6.0-P4.50-LS6.5")
      (description "电路结构:单刀单掷;按钮形状:圆形按钮;作用力:2.5N;安装方式:-;开关长度:6mm;开关宽度:6mm;开关高度:8.5mm;带灯:-;工作寿命:-;")
      (fields (field (name "Manufacturer") "Yuandi(元迪)"))
      (libsource (lib "easyedapro") (part "TS-1095-A10B3-D1"))
    )
    (comp (ref "SW5")
      (value "TS-1095-A10B3-D1")
      (footprint "easyedapro:SW-TH_4P-L6.0-W6.0-P4.50-LS6.5")
      (description "电路结构:单刀单掷;按钮形状:圆形按钮;作用力:2.5N;安装方式:-;开关长度:6mm;开关宽度:6mm;开关高度:8.5mm;带灯:-;工作寿命:-;")
      (fields (field (name "Manufacturer") "Yuandi(元迪)"))
      (libsource (lib "easyedapro") (part "TS-1095-A10B3-D1"))
    )
    (comp (ref "SW6")
      (value "TS-1095-A10B3-D1")
      (footprint "easyedapro:SW-TH_4P-L6.0-W6.0-P4.50-LS6.5")
      (description "电路结构:单刀单掷;按钮形状:圆形按钮;作用力:2.5N;安装方式:-;开关长度:6mm;开关宽度:6mm;开关高度:8.5mm;带灯:-;工作寿命:-;")
      (fields (field (name "Manufacturer") "Yuandi(元迪)"))
      (libsource (lib "easyedapro") (part "TS-1095-A10B3-D1"))
    )
    (comp (ref "SW7")
      (value "TS-1095-A10B3-D1")
      (footprint "easyedapro:SW-TH_4P-L6.0-W6.0-P4.50-LS6.5")
      (description "电路结构:单刀单掷;按钮形状:圆形按钮;作用力:2.5N;安装方式:-;开关长度:6mm;开关宽度:6mm;开关高度:8.5mm;带灯:-;工作寿命:-;")
      (fields (field (name "Manufacturer") "Yuandi(元迪)"))
      (libsource (lib "easyedapro") (part "TS-1095-A10B3-D1"))
    )
    (comp (ref "SW8")
      (value "TS-1095-A10B3-D1")
      (footprint "easyedapro:SW-TH_4P-L6.0-W6.0-P4.50-LS6.5")
      (description "电路结构:单刀单掷;按钮形状:圆形按钮;作用力:2.5N;安装方式:-;开关长度:6mm;开关宽度:6mm;开关高度:8.5mm;带灯:-;工作寿命:-;")
      (fields (field (name "Manufacturer") "Yuandi(元迪)"))
      (libsource (lib "easyedapro") (part "TS-1095-A10B3-D1"))
    )
    (comp (ref "SW9")
      (value "TS-1095-A10B3-D1")
      (footprint "easyedapro:SW-TH_4P-L6.0-W6.0-P4.50-LS6.5")
      (description "电路结构:单刀单掷;按钮形状:圆形按钮;作用力:2.5N;安装方式:-;开关长度:6mm;开关宽度:6mm;开关高度:8.5mm;带灯:-;工作寿命:-;")
      (fields (field (name "Manufacturer") "Yuandi(元迪)"))
      (libsource (lib "easyedapro") (part "TS-1095-A10B3-D1"))
    )
    (comp (ref "SW12")
      (value "XKB7070-Z")
      (footprint "easyedapro:SW-TH_6P-L7.0-W7.0-P2.00")
      (description "自锁/无锁:自锁;安装方式:直插;触点电流:100mA;额定电压:30V;带灯:不带;作用力:1.6N;工作寿命:10万次;")
      (fields (field (name "Manufacturer") "XKB Connection(中国星坤)"))
      (libsource (lib "easyedapro") (part "XKB7070-Z"))
    )
    (comp (ref "U1")
      (value "OPA320AQDBVRQ1")
      (footprint "easyedapro:SOT-23-5_L2.9-W1.6-P0.95-LS2.8-BR")
      (description "放大器数:单路;增益带宽积(GBP):20MHz;输入偏置电流(Ib):0.2pA;压摆率(SR):10V/us;带宽(-3db):-;轨到轨:-;")
      (fields (field (name "Manufacturer") "TI(德州仪器)"))
      (libsource (lib "easyedapro") (part "OPA320AQDBVRQ1"))
    )
    (comp (ref "U2")
      (value "AMC1311BDWVR")
      (footprint "easyedapro:SOIC-8_L7.5-W5.9-P1.27-LS11.5-BL")
      (description "AMC1311 2V 输入、精密电压检测增强型隔离式放大器")
      (fields (field (name "Manufacturer") "TI(德州仪器)"))
      (libsource (lib "easyedapro") (part "AMC1311BDWVR"))
    )
    (comp (ref "U5")
      (value "X6511FV-26-C85D32")
      (footprint "easyedapro:HDR-TH_26P-P2.54-V-F")
      (fields (field (name "Manufacturer") "XKB Connection(中国星坤)"))
      (libsource (lib "easyedapro") (part "X6511FV-26-C85D32"))
    )
    (comp (ref "U6")
      (value "X6511FV-26-C85D32")
      (footprint "easyedapro:HDR-TH_26P-P2.54-V-F")
      (fields (field (name "Manufacturer") "XKB Connection(中国星坤)"))
      (libsource (lib "easyedapro") (part "X6511FV-26-C85D32"))
    )
    (comp (ref "U7")
      (value "X6511FV-26-C85D32")
      (footprint "easyedapro:HDR-TH_26P-P2.54-V-F")
      (fields (field (name "Manufacturer") "XKB Connection(中国星坤)"))
      (libsource (lib "easyedapro") (part "X6511FV-26-C85D32"))
    )
    (comp (ref "U8")
      (value "X6511FV-26-C85D32")
      (footprint "easyedapro:HDR-TH_26P-P2.54-V-F")
      (fields (field (name "Manufacturer") "XKB Connection(中国星坤)"))
      (libsource (lib "easyedapro") (part "X6511FV-26-C85D32"))
    )
    (comp (ref "U9")
      (value "PM2.54-1*5")
      (footprint "easyedapro:HDR-TH_5P-P2.54-V-F")
      (fields (field (name "Manufacturer") "ZHOURI(洲日)"))
      (libsource (lib "easyedapro") (part "PM2.54-1*5"))
    )
    (comp (ref "U10")
      (value "PM2.54-1*5")
      (footprint "easyedapro:HDR-TH_5P-P2.54-V-F")
      (fields (field (name "Manufacturer") "ZHOURI(洲日)"))
      (libsource (lib "easyedapro") (part "PM2.54-1*5"))
    )
    (comp (ref "U18")
      (value "TPS5430DDAR")
      (footprint "easyedapro:ESOP-8_L4.9-W3.9-P1.27-LS6.0-TL-EP")
      (description "功能类型:降压型;输出类型:可调;工作电压:5.5V~36V;输出电压:1.221V~32.04V;输出电流:3A;")
      (fields (field (name "Manufacturer") "TI(德州仪器)"))
      (libsource (lib "easyedapro") (part "TPS5430DDAR"))
    )
    (comp (ref "U19")
      (value "TLV76733DRVR")
      (footprint "easyedapro:WSON-6_L2.0-W2.0-P0.65-TL-EP")
      (description "输出类型:固定;最大输入电压:16V;输出电压:3.3V;输出电流:1A;电源纹波抑制比(PSRR):70dB@(120Hz);输出极性:正极;")
      (fields (field (name "Manufacturer") "TI(德州仪器)"))
      (libsource (lib "easyedapro") (part "TLV76733DRVR"))
    )
    (comp (ref "U20")
      (value "B0505S-1WR3")
      (footprint "easyedapro:PWRM-TH_B0505S-1WR3")
      (fields (field (name "Manufacturer") "EVISUN(易成)"))
      (libsource (lib "easyedapro") (part "B0505S-1WR3_C7465178"))
    )
    (comp (ref "U21")
      (value "OPA320AQDBVRQ1")
      (footprint "easyedapro:SOT-23-5_L2.9-W1.6-P0.95-LS2.8-BR")
      (description "放大器数:单路;增益带宽积(GBP):20MHz;输入偏置电流(Ib):0.2pA;压摆率(SR):10V/us;带宽(-3db):-;轨到轨:-;")
      (fields (field (name "Manufacturer") "TI(德州仪器)"))
      (libsource (lib "easyedapro") (part "OPA320AQDBVRQ1"))
    )
    (comp (ref "U22")
      (value "AMC1311BDWVR")
      (footprint "easyedapro:SOIC-8_L7.5-W5.9-P1.27-LS11.5-BL")
      (description "AMC1311 2V 输入、精密电压检测增强型隔离式放大器")
      (fields (field (name "Manufacturer") "TI(德州仪器)"))
      (libsource (lib "easyedapro") (part "AMC1311BDWVR"))
    )
    (comp (ref "U30")
      (value "HS96L03W2C03")
      (footprint "easyedapro:OLED-TH_L27.8-W27.2-P2.54_C9900033791")
      (description "核心芯片:SSD1315芯片;接口类型:I2C;尺寸(inch):0.96;像素分辨率:128x64;")
      (fields (field (name "Manufacturer") "HS(汉昇)"))
      (libsource (lib "easyedapro") (part "HS96L03W2C03"))
    )
    (comp (ref "U35")
      (value "HX PZ2.54-1x2P ZZ")
      (footprint "easyedapro:HDR-TH_2P-P2.54-V-M-3")
      (fields (field (name "Manufacturer") "hanxia(韩下)"))
      (libsource (lib "easyedapro") (part "HX PZ2.54-1X2P ZZ"))
    )
    (comp (ref "U36")
      (value "HX PZ2.54-1x2P ZZ")
      (footprint "easyedapro:HDR-TH_2P-P2.54-V-M-3")
      (fields (field (name "Manufacturer") "hanxia(韩下)"))
      (libsource (lib "easyedapro") (part "HX PZ2.54-1X2P ZZ"))
    )
    (comp (ref "U37")
      (value "HX PZ2.54-1x2P ZZ")
      (footprint "easyedapro:HDR-TH_2P-P2.54-V-M-3")
      (fields (field (name "Manufacturer") "hanxia(韩下)"))
      (libsource (lib "easyedapro") (part "HX PZ2.54-1X2P ZZ"))
    )
    (comp (ref "U38")
      (value "HX PZ2.54-1x2P ZZ")
      (footprint "easyedapro:HDR-TH_2P-P2.54-V-M-3")
      (fields (field (name "Manufacturer") "hanxia(韩下)"))
      (libsource (lib "easyedapro") (part "HX PZ2.54-1X2P ZZ"))
    )
    (comp (ref "U39")
      (value "HX PZ2.54-1x2P ZZ")
      (footprint "easyedapro:HDR-TH_2P-P2.54-V-M-3")
      (fields (field (name "Manufacturer") "hanxia(韩下)"))
      (libsource (lib "easyedapro") (part "HX PZ2.54-1X2P ZZ"))
    )
    (comp (ref "U40")
      (value "HX PZ2.54-1x2P ZZ")
      (footprint "easyedapro:HDR-TH_2P-P2.54-V-M-3")
      (fields (field (name "Manufacturer") "hanxia(韩下)"))
      (libsource (lib "easyedapro") (part "HX PZ2.54-1X2P ZZ"))
    )
    (comp (ref "U41")
      (value "HX PZ2.54-1x2P ZZ")
      (footprint "easyedapro:HDR-TH_2P-P2.54-V-M-3")
      (fields (field (name "Manufacturer") "hanxia(韩下)"))
      (libsource (lib "easyedapro") (part "HX PZ2.54-1X2P ZZ"))
    )
    (comp (ref "U42")
      (value "HX PZ2.54-1x2P ZZ")
      (footprint "easyedapro:HDR-TH_2P-P2.54-V-M-3")
      (fields (field (name "Manufacturer") "hanxia(韩下)"))
      (libsource (lib "easyedapro") (part "HX PZ2.54-1X2P ZZ"))
    )
    (comp (ref "U43")
      (value "HX PZ2.54-1x2P ZZ")
      (footprint "easyedapro:HDR-TH_2P-P2.54-V-M-3")
      (fields (field (name "Manufacturer") "hanxia(韩下)"))
      (libsource (lib "easyedapro") (part "HX PZ2.54-1X2P ZZ"))
    )
    (comp (ref "U44")
      (value "HX PZ2.54-1x2P ZZ")
      (footprint "easyedapro:HDR-TH_2P-P2.54-V-M-3")
      (fields (field (name "Manufacturer") "hanxia(韩下)"))
      (libsource (lib "easyedapro") (part "HX PZ2.54-1X2P ZZ"))
    )
    (comp (ref "U45")
      (value "HX PZ2.54-1x2P ZZ")
      (footprint "easyedapro:HDR-TH_2P-P2.54-V-M-3")
      (fields (field (name "Manufacturer") "hanxia(韩下)"))
      (libsource (lib "easyedapro") (part "HX PZ2.54-1X2P ZZ"))
    )
  )
  (nets
    (net (code "1") (name "+3V3") (class "Default")
      (node (ref "C62") (pin "2") (pinfunction "2_2") (pintype "input"))
      (node (ref "D1") (pin "2") (pinfunction "K2_2") (pintype "unspecified"))
      (node (ref "D4") (pin "2") (pinfunction "K2_2") (pintype "unspecified"))
      (node (ref "R61") (pin "2") (pinfunction "2_2") (pintype "input"))
      (node (ref "R62") (pin "2") (pinfunction "2_2") (pintype "input"))
      (node (ref "R64") (pin "2") (pinfunction "2_2") (pintype "input"))
      (node (ref "U19") (pin "1") (pinfunction "OUT_1") (pintype "unspecified"))
      (node (ref "U19") (pin "2") (pinfunction "FB/SNS_2") (pintype "unspecified"))
      (node (ref "U30") (pin "2") (pinfunction "VCC_2") (pintype "unspecified"))
      (node (ref "U37") (pin "1") (pinfunction "1_1") (pintype "unspecified"))
      (node (ref "U40") (pin "1") (pinfunction "1_1") (pintype "unspecified"))
      (node (ref "U43") (pin "1") (pinfunction "1_1") (pintype "unspecified"))
    )
    (net (code "2") (name "+5VA") (class "Default")
      (node (ref "C73") (pin "1") (pinfunction "1_1") (pintype "input"))
      (node (ref "C75") (pin "2") (pinfunction "2_2") (pintype "unspecified"))
      (node (ref "C76") (pin "2") (pinfunction "2_2") (pintype "unspecified"))
      (node (ref "C77") (pin "2") (pinfunction "2_2") (pintype "unspecified"))
      (node (ref "C85") (pin "2") (pinfunction "2_2") (pintype "unspecified"))
      (node (ref "C86") (pin "2") (pinfunction "2_2") (pintype "unspecified"))
      (node (ref "U2") (pin "1") (pinfunction "VDD1_1") (pintype "unspecified"))
      (node (ref "U20") (pin "4") (pinfunction "+Vout_4") (pintype "unspecified"))
      (node (ref "U22") (pin "1") (pinfunction "VDD1_1") (pintype "unspecified"))
    )
    (net (code "3") (name "+12V") (class "Default")
      (node (ref "C66") (pin "2") (pinfunction "2_2") (pintype "unspecified"))
      (node (ref "C67") (pin "2") (pinfunction "2_2") (pintype "unspecified"))
      (node (ref "CN1") (pin "3") (pinfunction "3_3") (pintype "unspecified"))
      (node (ref "CN1") (pin "6") (pinfunction "6_6") (pintype "unspecified"))
      (node (ref "CN2") (pin "3") (pinfunction "3_3") (pintype "unspecified"))
      (node (ref "CN2") (pin "6") (pinfunction "6_6") (pintype "unspecified"))
      (node (ref "CN3") (pin "3") (pinfunction "3_3") (pintype "unspecified"))
      (node (ref "CN3") (pin "6") (pinfunction "6_6") (pintype "unspecified"))
      (node (ref "SW12") (pin "1") (pinfunction "1_1") (pintype "unspecified"))
      (node (ref "U18") (pin "7") (pinfunction "VIN_7") (pintype "unspecified"))
      (node (ref "U35") (pin "1") (pinfunction "1_1") (pintype "unspecified"))
      (node (ref "U38") (pin "1") (pinfunction "1_1") (pintype "unspecified"))
      (node (ref "U41") (pin "1") (pinfunction "1_1") (pintype "unspecified"))
    )
    (net (code "4") (name "/AD0IN2") (class "Default")
      (node (ref "U5") (pin "6") (pinfunction "6_6") (pintype "unspecified"))
    )
    (net (code "5") (name "/AD0IN3") (class "Default")
      (node (ref "U6") (pin "6") (pinfunction "6_6") (pintype "unspecified"))
    )
    (net (code "6") (name "/AD0IN4") (class "Default")
      (node (ref "U5") (pin "7") (pinfunction "7_7") (pintype "unspecified"))
    )
    (net (code "7") (name "/AD0IN5") (class "Default")
      (node (ref "U6") (pin "7") (pinfunction "7_7") (pintype "unspecified"))
    )
    (net (code "8") (name "/AD0IN6") (class "Default")
      (node (ref "U5") (pin "8") (pinfunction "8_8") (pintype "unspecified"))
    )
    (net (code "9") (name "/AD0IN7") (class "Default")
      (node (ref "U6") (pin "8") (pinfunction "8_8") (pintype "unspecified"))
    )
    (net (code "10") (name "/AD1IN2") (class "Default")
      (node (ref "U6") (pin "3") (pinfunction "3_3") (pintype "unspecified"))
    )
    (net (code "11") (name "/AD1IN3") (class "Default")
      (node (ref "U5") (pin "3") (pinfunction "3_3") (pintype "unspecified"))
    )
    (net (code "12") (name "/AD1IN4") (class "Default")
      (node (ref "U6") (pin "2") (pinfunction "2_2") (pintype "unspecified"))
    )
    (net (code "13") (name "/AD1IN5") (class "Default")
      (node (ref "U5") (pin "2") (pinfunction "2_2") (pintype "unspecified"))
    )
    (net (code "14") (name "/AD1IN6") (class "Default")
      (node (ref "U6") (pin "1") (pinfunction "1_1") (pintype "unspecified"))
    )
    (net (code "15") (name "/AD1IN7") (class "Default")
      (node (ref "U5") (pin "1") (pinfunction "1_1") (pintype "unspecified"))
    )
    (net (code "16") (name "/GPIO15") (class "Default")
      (node (ref "U5") (pin "10") (pinfunction "10_10") (pintype "unspecified"))
    )
    (net (code "17") (name "/GPIO16") (class "Default")
      (node (ref "U6") (pin "9") (pinfunction "9_9") (pintype "unspecified"))
    )
    (net (code "18") (name "/GPIO17") (class "Default")
      (node (ref "U5") (pin "9") (pinfunction "9_9") (pintype "unspecified"))
    )
    (net (code "19") (name "/GPIO18") (class "Default")
      (node (ref "U8") (pin "1") (pinfunction "1_1") (pintype "unspecified"))
    )
    (net (code "20") (name "/GPIO19") (class "Default")
      (node (ref "U7") (pin "1") (pinfunction "1_1") (pintype "unspecified"))
    )
    (net (code "21") (name "/GPIO20") (class "Default")
      (node (ref "U8") (pin "2") (pinfunction "2_2") (pintype "unspecified"))
    )
    (net (code "22") (name "/GPIO21") (class "Default")
      (node (ref "U7") (pin "2") (pinfunction "2_2") (pintype "unspecified"))
    )
    (net (code "23") (name "/GPIO22") (class "Default")
      (node (ref "U8") (pin "3") (pinfunction "3_3") (pintype "unspecified"))
    )
    (net (code "24") (name "/GPIO23") (class "Default")
      (node (ref "U7") (pin "3") (pinfunction "3_3") (pintype "unspecified"))
    )
    (net (code "25") (name "/GPIO24") (class "Default")
      (node (ref "U8") (pin "4") (pinfunction "4_4") (pintype "unspecified"))
    )
    (net (code "26") (name "/GPIO25") (class "Default")
      (node (ref "U7") (pin "4") (pinfunction "4_4") (pintype "unspecified"))
    )
    (net (code "27") (name "/GPIO26") (class "Default")
      (node (ref "U8") (pin "5") (pinfunction "5_5") (pintype "unspecified"))
    )
    (net (code "28") (name "/GPIO27") (class "Default")
      (node (ref "U7") (pin "5") (pinfunction "5_5") (pintype "unspecified"))
    )
    (net (code "29") (name "/GPIO28") (class "Default")
      (node (ref "U7") (pin "23") (pinfunction "23_23") (pintype "unspecified"))
    )
    (net (code "30") (name "/GPIO29") (class "Default")
      (node (ref "U5") (pin "18") (pinfunction "18_18") (pintype "unspecified"))
    )
    (net (code "31") (name "/GPIO30") (class "Default")
      (node (ref "U6") (pin "18") (pinfunction "18_18") (pintype "unspecified"))
    )
    (net (code "32") (name "/GPIO31") (class "Default")
      (node (ref "U5") (pin "19") (pinfunction "19_19") (pintype "unspecified"))
    )
    (net (code "33") (name "/GPIO34") (class "Default")
      (node (ref "U8") (pin "24") (pinfunction "24_24") (pintype "unspecified"))
    )
    (net (code "34") (name "/GPIO35") (class "Default")
      (node (ref "U8") (pin "25") (pinfunction "25_25") (pintype "unspecified"))
    )
    (net (code "35") (name "/GPIO36") (class "Default")
      (node (ref "U7") (pin "24") (pinfunction "24_24") (pintype "unspecified"))
    )
    (net (code "36") (name "/GPIO37") (class "Default")
      (node (ref "U7") (pin "25") (pinfunction "25_25") (pintype "unspecified"))
    )
    (net (code "37") (name "/GPIO38") (class "Default")
      (node (ref "U8") (pin "23") (pinfunction "23_23") (pintype "unspecified"))
    )
    (net (code "38") (name "/GPIO39") (class "Default")
      (node (ref "U6") (pin "19") (pinfunction "19_19") (pintype "unspecified"))
    )
    (net (code "39") (name "/GPIO40") (class "Default")
      (node (ref "U8") (pin "26") (pinfunction "26_26") (pintype "unspecified"))
    )
    (net (code "40") (name "/GPIO41") (class "Default")
      (node (ref "U7") (pin "26") (pinfunction "26_26") (pintype "unspecified"))
    )
    (net (code "41") (name "/GPIO42") (class "Default")
      (node (ref "U6") (pin "26") (pinfunction "26_26") (pintype "unspecified"))
    )
    (net (code "42") (name "/GPIO43") (class "Default")
      (node (ref "U5") (pin "26") (pinfunction "26_26") (pintype "unspecified"))
    )
    (net (code "43") (name "/GPIO44") (class "Default")
      (node (ref "U6") (pin "25") (pinfunction "25_25") (pintype "unspecified"))
    )
    (net (code "44") (name "/GPIO45") (class "Default")
      (node (ref "U5") (pin "25") (pinfunction "25_25") (pintype "unspecified"))
    )
    (net (code "45") (name "/GPIO46") (class "Default")
      (node (ref "U6") (pin "24") (pinfunction "24_24") (pintype "unspecified"))
    )
    (net (code "46") (name "/GPIO47") (class "Default")
      (node (ref "U5") (pin "24") (pinfunction "24_24") (pintype "unspecified"))
    )
    (net (code "47") (name "/GPIO51") (class "Default")
      (node (ref "U7") (pin "8") (pinfunction "8_8") (pintype "unspecified"))
    )
    (net (code "48") (name "/GPIO52") (class "Default")
      (node (ref "U8") (pin "9") (pinfunction "9_9") (pintype "unspecified"))
    )
    (net (code "49") (name "/GPIO53") (class "Default")
      (node (ref "U7") (pin "9") (pinfunction "9_9") (pintype "unspecified"))
    )
    (net (code "50") (name "/GPIO54") (class "Default")
      (node (ref "U8") (pin "10") (pinfunction "10_10") (pintype "unspecified"))
    )
    (net (code "51") (name "/GPIO55") (class "Default")
      (node (ref "U7") (pin "10") (pinfunction "10_10") (pintype "unspecified"))
    )
    (net (code "52") (name "/GPIO56") (class "Default")
      (node (ref "U8") (pin "11") (pinfunction "11_11") (pintype "unspecified"))
    )
    (net (code "53") (name "/GPIO57") (class "Default")
      (node (ref "U7") (pin "11") (pinfunction "11_11") (pintype "unspecified"))
    )
    (net (code "54") (name "/GPIO58") (class "Default")
      (node (ref "U8") (pin "12") (pinfunction "12_12") (pintype "unspecified"))
    )
    (net (code "55") (name "/GPIO59") (class "Default")
      (node (ref "U7") (pin "12") (pinfunction "12_12") (pintype "unspecified"))
    )
    (net (code "56") (name "/GPIO60") (class "Default")
      (node (ref "U8") (pin "13") (pinfunction "13_13") (pintype "unspecified"))
    )
    (net (code "57") (name "/GPIO61") (class "Default")
      (node (ref "U7") (pin "13") (pinfunction "13_13") (pintype "unspecified"))
    )
    (net (code "58") (name "/GPIO62") (class "Default")
      (node (ref "U8") (pin "14") (pinfunction "14_14") (pintype "unspecified"))
    )
    (net (code "59") (name "/GPIO63") (class "Default")
      (node (ref "U7") (pin "14") (pinfunction "14_14") (pintype "unspecified"))
    )
    (net (code "60") (name "/GPIO69") (class "Default")
      (node (ref "U7") (pin "17") (pinfunction "17_17") (pintype "unspecified"))
    )
    (net (code "61") (name "/GPIO70") (class "Default")
      (node (ref "U8") (pin "18") (pinfunction "18_18") (pintype "unspecified"))
    )
    (net (code "62") (name "/GPIO71") (class "Default")
      (node (ref "U7") (pin "18") (pinfunction "18_18") (pintype "unspecified"))
    )
    (net (code "63") (name "/GPIO72") (class "Default")
      (node (ref "U8") (pin "19") (pinfunction "19_19") (pintype "unspecified"))
    )
    (net (code "64") (name "/GPIO73") (class "Default")
      (node (ref "U7") (pin "19") (pinfunction "19_19") (pintype "unspecified"))
    )
    (net (code "65") (name "/GPIO74") (class "Default")
      (node (ref "U8") (pin "20") (pinfunction "20_20") (pintype "unspecified"))
    )
    (net (code "66") (name "/GPIO75") (class "Default")
      (node (ref "U7") (pin "20") (pinfunction "20_20") (pintype "unspecified"))
    )
    (net (code "67") (name "/GPIO76") (class "Default")
      (node (ref "U8") (pin "21") (pinfunction "21_21") (pintype "unspecified"))
    )
    (net (code "68") (name "/GPIO77") (class "Default")
      (node (ref "U7") (pin "21") (pinfunction "21_21") (pintype "unspecified"))
    )
    (net (code "69") (name "/GPIO78") (class "Default")
      (node (ref "U8") (pin "22") (pinfunction "22_22") (pintype "unspecified"))
    )
    (net (code "70") (name "/GPIO79") (class "Default")
      (node (ref "U7") (pin "22") (pinfunction "22_22") (pintype "unspecified"))
    )
    (net (code "71") (name "/GPIO80") (class "Default")
      (node (ref "U6") (pin "23") (pinfunction "23_23") (pintype "unspecified"))
    )
    (net (code "72") (name "/GPIO81") (class "Default")
      (node (ref "U5") (pin "23") (pinfunction "23_23") (pintype "unspecified"))
    )
    (net (code "73") (name "/GPIO82") (class "Default")
      (node (ref "U6") (pin "22") (pinfunction "22_22") (pintype "unspecified"))
    )
    (net (code "74") (name "/GPIO83") (class "Default")
      (node (ref "U5") (pin "22") (pinfunction "22_22") (pintype "unspecified"))
    )
    (net (code "75") (name "/GPIO84") (class "Default")
      (node (ref "U6") (pin "21") (pinfunction "21_21") (pintype "unspecified"))
    )
    (net (code "76") (name "/GPIO85") (class "Default")
      (node (ref "U5") (pin "21") (pinfunction "21_21") (pintype "unspecified"))
    )
    (net (code "77") (name "/GPIO86") (class "Default")
      (node (ref "U6") (pin "20") (pinfunction "20_20") (pintype "unspecified"))
    )
    (net (code "78") (name "/GPIO87") (class "Default")
      (node (ref "U5") (pin "20") (pinfunction "20_20") (pintype "unspecified"))
    )
    (net (code "79") (name "3V31") (class "Default")
      (node (ref "U10") (pin "4") (pinfunction "4_4") (pintype "unspecified"))
    )
    (net (code "80") (name "3V32") (class "Default")
      (node (ref "U9") (pin "4") (pinfunction "4_4") (pintype "unspecified"))
    )
    (net (code "81") (name "5V1") (class "Default")
      (node (ref "C69") (pin "1") (pinfunction "1_1") (pintype "input"))
      (node (ref "C70") (pin "2") (pinfunction "2_2") (pintype "unspecified"))
      (node (ref "C71") (pin "2") (pinfunction "2_2") (pintype "unspecified"))
      (node (ref "C72") (pin "2") (pinfunction "2_2") (pintype "input"))
      (node (ref "C74") (pin "2") (pinfunction "2_2") (pintype "unspecified"))
      (node (ref "C82") (pin "2") (pinfunction "2_2") (pintype "unspecified"))
      (node (ref "C83") (pin "2") (pinfunction "2_2") (pintype "unspecified"))
      (node (ref "C91") (pin "2") (pinfunction "2_2") (pintype "unspecified"))
      (node (ref "C92") (pin "2") (pinfunction "2_2") (pintype "unspecified"))
      (node (ref "C93") (pin "2") (pinfunction "2_2") (pintype "unspecified"))
      (node (ref "FB2") (pin "1") (pinfunction "1_1") (pintype "unspecified"))
      (node (ref "FB3") (pin "1") (pinfunction "1_1") (pintype "unspecified"))
      (node (ref "L3") (pin "2") (pinfunction "2_2") (pintype "input"))
      (node (ref "R67") (pin "2") (pinfunction "2_2") (pintype "input"))
      (node (ref "R82") (pin "2") (pinfunction "2_2") (pintype "input"))
      (node (ref "U10") (pin "1") (pinfunction "1_1") (pintype "unspecified"))
      (node (ref "U19") (pin "4") (pinfunction "EN_4") (pintype "unspecified"))
      (node (ref "U19") (pin "6") (pinfunction "IN_6") (pintype "unspecified"))
      (node (ref "U2") (pin "8") (pinfunction "VDD2_8") (pintype "unspecified"))
      (node (ref "U20") (pin "2") (pinfunction "+Vin_2") (pintype "unspecified"))
      (node (ref "U22") (pin "8") (pinfunction "VDD2_8") (pintype "unspecified"))
      (node (ref "U36") (pin "1") (pinfunction "1_1") (pintype "unspecified"))
      (node (ref "U39") (pin "1") (pinfunction "1_1") (pintype "unspecified"))
      (node (ref "U42") (pin "1") (pinfunction "1_1") (pintype "unspecified"))
    )
    (net (code "82") (name "5V2") (class "Default")
      (node (ref "U9") (pin "1") (pinfunction "1_1") (pintype "unspecified"))
    )
    (net (code "83") (name "200ADC") (class "Default")
      (node (ref "C81") (pin "2") (pinfunction "2_2") (pintype "unspecified"))
      (node (ref "D1") (pin "3") (pinfunction "A_3") (pintype "unspecified"))
      (node (ref "H1") (pin "1") (pinfunction "1_1") (pintype "unspecified"))
      (node (ref "R5") (pin "1") (pinfunction "1_1") (pintype "unspecified"))
    )
    (net (code "84") (name "400ADC") (class "Default")
      (node (ref "C90") (pin "2") (pinfunction "2_2") (pintype "unspecified"))
      (node (ref "D4") (pin "3") (pinfunction "A_3") (pintype "unspecified"))
      (node (ref "H1") (pin "3") (pinfunction "3_3") (pintype "unspecified"))
      (node (ref "R72") (pin "1") (pinfunction "1_1") (pintype "unspecified"))
    )
    (net (code "85") (name "AD0IN0") (class "Default")
      (node (ref "H1") (pin "16") (pinfunction "16_16") (pintype "unspecified"))
      (node (ref "H1") (pin "2") (pinfunction "2_2") (pintype "unspecified"))
      (node (ref "U5") (pin "5") (pinfunction "5_5") (pintype "unspecified"))
    )
    (net (code "86") (name "AD0IN1") (class "Default")
      (node (ref "H1") (pin "14") (pinfunction "14_14") (pintype "unspecified"))
      (node (ref "H1") (pin "4") (pinfunction "4_4") (pintype "unspecified"))
      (node (ref "U6") (pin "5") (pinfunction "5_5") (pintype "unspecified"))
    )
    (net (code "87") (name "AD1IN0") (class "Default")
      (node (ref "H1") (pin "12") (pinfunction "12_12") (pintype "unspecified"))
      (node (ref "H1") (pin "6") (pinfunction "6_6") (pintype "unspecified"))
      (node (ref "U6") (pin "4") (pinfunction "4_4") (pintype "unspecified"))
    )
    (net (code "88") (name "AD1IN1") (class "Default")
      (node (ref "H1") (pin "10") (pinfunction "10_10") (pintype "unspecified"))
      (node (ref "H1") (pin "8") (pinfunction "8_8") (pintype "unspecified"))
      (node (ref "U5") (pin "4") (pinfunction "4_4") (pintype "unspecified"))
    )
    (net (code "89") (name "AGND") (class "Default")
      (node (ref "C73") (pin "2") (pinfunction "2_2") (pintype "input"))
      (node (ref "C75") (pin "1") (pinfunction "1_1") (pintype "unspecified"))
      (node (ref "C76") (pin "1") (pinfunction "1_1") (pintype "unspecified"))
      (node (ref "C77") (pin "1") (pinfunction "1_1") (pintype "unspecified"))
      (node (ref "C78") (pin "1") (pinfunction "1_1") (pintype "input"))
      (node (ref "C85") (pin "1") (pinfunction "1_1") (pintype "unspecified"))
      (node (ref "C86") (pin "1") (pinfunction "1_1") (pintype "unspecified"))
      (node (ref "C87") (pin "1") (pinfunction "1_1") (pintype "input"))
      (node (ref "U2") (pin "3") (pinfunction "SHTDN_3") (pintype "unspecified"))
      (node (ref "U2") (pin "4") (pinfunction "GND1_4") (pintype "unspecified"))
      (node (ref "U20") (pin "3") (pinfunction "-Vout_3") (pintype "unspecified"))
      (node (ref "U22") (pin "3") (pinfunction "SHTDN_3") (pintype "unspecified"))
      (node (ref "U22") (pin "4") (pinfunction "GND1_4") (pintype "unspecified"))
      (node (ref "U44") (pin "2") (pinfunction "2_2") (pintype "unspecified"))
      (node (ref "U45") (pin "2") (pinfunction "2_2") (pintype "unspecified"))
    )
    (net (code "90") (name "AGND1") (class "Default")
      (node (ref "C72") (pin "1") (pinfunction "1_1") (pintype "input"))
      (node (ref "C74") (pin "1") (pinfunction "1_1") (pintype "unspecified"))
      (node (ref "C80") (pin "1") (pinfunction "1_1") (pintype "input"))
      (node (ref "C81") (pin "1") (pinfunction "1_1") (pintype "unspecified"))
      (node (ref "C82") (pin "1") (pinfunction "1_1") (pintype "unspecified"))
      (node (ref "C83") (pin "1") (pinfunction "1_1") (pintype "unspecified"))
      (node (ref "C89") (pin "1") (pinfunction "1_1") (pintype "input"))
      (node (ref "C90") (pin "1") (pinfunction "1_1") (pintype "unspecified"))
      (node (ref "C91") (pin "1") (pinfunction "1_1") (pintype "unspecified"))
      (node (ref "C92") (pin "1") (pinfunction "1_1") (pintype "unspecified"))
      (node (ref "R4") (pin "1") (pinfunction "1_1") (pintype "unspecified"))
      (node (ref "R70") (pin "1") (pinfunction "1_1") (pintype "unspecified"))
      (node (ref "U1") (pin "2") (pinfunction "V-_2") (pintype "unspecified"))
      (node (ref "U10") (pin "5") (pinfunction "5_5") (pintype "unspecified"))
      (node (ref "U2") (pin "5") (pinfunction "GND2_5") (pintype "unspecified"))
      (node (ref "U20") (pin "1") (pinfunction "-Vin_1") (pintype "unspecified"))
      (node (ref "U21") (pin "2") (pinfunction "V-_2") (pintype "unspecified"))
      (node (ref "U22") (pin "5") (pinfunction "GND2_5") (pintype "unspecified"))
    )
    (net (code "91") (name "AGND2") (class "Default")
      (node (ref "U9") (pin "5") (pinfunction "5_5") (pintype "unspecified"))
    )
    (net (code "92") (name "GND1") (class "Default")
      (node (ref "C62") (pin "1") (pinfunction "1_1") (pintype "input"))
      (node (ref "C66") (pin "1") (pinfunction "1_1") (pintype "unspecified"))
      (node (ref "C67") (pin "1") (pinfunction "1_1") (pintype "unspecified"))
      (node (ref "C69") (pin "2") (pinfunction "2_2") (pintype "input"))
      (node (ref "C70") (pin "1") (pinfunction "1_1") (pintype "unspecified"))
      (node (ref "C71") (pin "1") (pinfunction "1_1") (pintype "unspecified"))
      (node (ref "C93") (pin "1") (pinfunction "1_1") (pintype "unspecified"))
      (node (ref "CN1") (pin "4") (pinfunction "4_4") (pintype "unspecified"))
      (node (ref "CN1") (pin "5") (pinfunction "5_5") (pintype "unspecified"))
      (node (ref "CN2") (pin "4") (pinfunction "4_4") (pintype "unspecified"))
      (node (ref "CN2") (pin "5") (pinfunction "5_5") (pintype "unspecified"))
      (node (ref "CN3") (pin "4") (pinfunction "4_4") (pintype "unspecified"))
      (node (ref "CN3") (pin "5") (pinfunction "5_5") (pintype "unspecified"))
      (node (ref "D1") (pin "1") (pinfunction "K1_1") (pintype "unspecified"))
      (node (ref "D3") (pin "2") (pinfunction "A_2") (pintype "unspecified"))
      (node (ref "D4") (pin "1") (pinfunction "K1_1") (pintype "unspecified"))
      (node (ref "DC1") (pin "2") (pinfunction "2_2") (pintype "unspecified"))
      (node (ref "DC1") (pin "3") (pinfunction "3_3") (pintype "unspecified"))
      (node (ref "H1") (pin "11") (pinfunction "11_11") (pintype "unspecified"))
      (node (ref "H1") (pin "13") (pinfunction "13_13") (pintype "unspecified"))
      (node (ref "H1") (pin "15") (pinfunction "15_15") (pintype "unspecified"))
      (node (ref "H1") (pin "5") (pinfunction "5_5") (pintype "unspecified"))
      (node (ref "H1") (pin "7") (pinfunction "7_7") (pintype "unspecified"))
      (node (ref "H1") (pin "9") (pinfunction "9_9") (pintype "unspecified"))
      (node (ref "LED10") (pin "2") (pinfunction "-_2") (pintype "unspecified"))
      (node (ref "LED11") (pin "2") (pinfunction "-_2") (pintype "unspecified"))
      (node (ref "LED6") (pin "2") (pinfunction "-_2") (pintype "unspecified"))
      (node (ref "LED7") (pin "2") (pinfunction "-_2") (pintype "unspecified"))
      (node (ref "LED8") (pin "2") (pinfunction "-_2") (pintype "unspecified"))
      (node (ref "LED9") (pin "2") (pinfunction "-_2") (pintype "unspecified"))
      (node (ref "R66") (pin "1") (pinfunction "1_1") (pintype "unspecified"))
      (node (ref "U10") (pin "3") (pinfunction "3_3") (pintype "unspecified"))
      (node (ref "U18") (pin "6") (pinfunction "GND_6") (pintype "unspecified"))
      (node (ref "U18") (pin "9") (pinfunction "PowerPAD_9") (pintype "unspecified"))
      (node (ref "U19") (pin "3") (pinfunction "GND_3") (pintype "unspecified"))
      (node (ref "U19") (pin "5") (pinfunction "GND_5") (pintype "unspecified"))
      (node (ref "U19") (pin "7") (pinfunction "EP_7") (pintype "unspecified"))
      (node (ref "U30") (pin "1") (pinfunction "GND_1") (pintype "unspecified"))
      (node (ref "U35") (pin "2") (pinfunction "2_2") (pintype "unspecified"))
      (node (ref "U36") (pin "2") (pinfunction "2_2") (pintype "unspecified"))
      (node (ref "U37") (pin "2") (pinfunction "2_2") (pintype "unspecified"))
      (node (ref "U38") (pin "2") (pinfunction "2_2") (pintype "unspecified"))
      (node (ref "U39") (pin "2") (pinfunction "2_2") (pintype "unspecified"))
      (node (ref "U40") (pin "2") (pinfunction "2_2") (pintype "unspecified"))
      (node (ref "U41") (pin "2") (pinfunction "2_2") (pintype "unspecified"))
      (node (ref "U42") (pin "2") (pinfunction "2_2") (pintype "unspecified"))
      (node (ref "U43") (pin "2") (pinfunction "2_2") (pintype "unspecified"))
    )
    (net (code "93") (name "GND2") (class "Default")
      (node (ref "U9") (pin "3") (pinfunction "3_3") (pintype "unspecified"))
    )
    (net (code "94") (name "GPIO0") (class "Default")
      (node (ref "CN1") (pin "1") (pinfunction "1_1") (pintype "unspecified"))
      (node (ref "U6") (pin "17") (pinfunction "17_17") (pintype "unspecified"))
    )
    (net (code "95") (name "GPIO1") (class "Default")
      (node (ref "CN1") (pin "2") (pinfunction "2_2") (pintype "unspecified"))
      (node (ref "U5") (pin "17") (pinfunction "17_17") (pintype "unspecified"))
    )
    (net (code "96") (name "GPIO2") (class "Default")
      (node (ref "CN1") (pin "8") (pinfunction "8_8") (pintype "unspecified"))
      (node (ref "U6") (pin "16") (pinfunction "16_16") (pintype "unspecified"))
    )
    (net (code "97") (name "GPIO3") (class "Default")
      (node (ref "CN1") (pin "7") (pinfunction "7_7") (pintype "unspecified"))
      (node (ref "U5") (pin "16") (pinfunction "16_16") (pintype "unspecified"))
    )
    (net (code "98") (name "GPIO4") (class "Default")
      (node (ref "CN2") (pin "1") (pinfunction "1_1") (pintype "unspecified"))
      (node (ref "U6") (pin "15") (pinfunction "15_15") (pintype "unspecified"))
    )
    (net (code "99") (name "GPIO5") (class "Default")
      (node (ref "CN2") (pin "2") (pinfunction "2_2") (pintype "unspecified"))
      (node (ref "U5") (pin "15") (pinfunction "15_15") (pintype "unspecified"))
    )
    (net (code "100") (name "GPIO6") (class "Default")
      (node (ref "CN2") (pin "8") (pinfunction "8_8") (pintype "unspecified"))
      (node (ref "U6") (pin "14") (pinfunction "14_14") (pintype "unspecified"))
    )
    (net (code "101") (name "GPIO7") (class "Default")
      (node (ref "CN2") (pin "7") (pinfunction "7_7") (pintype "unspecified"))
      (node (ref "U5") (pin "14") (pinfunction "14_14") (pintype "unspecified"))
    )
    (net (code "102") (name "GPIO8") (class "Default")
      (node (ref "CN3") (pin "1") (pinfunction "1_1") (pintype "unspecified"))
      (node (ref "U6") (pin "13") (pinfunction "13_13") (pintype "unspecified"))
    )
    (net (code "103") (name "GPIO9") (class "Default")
      (node (ref "CN3") (pin "2") (pinfunction "2_2") (pintype "unspecified"))
      (node (ref "U5") (pin "13") (pinfunction "13_13") (pintype "unspecified"))
    )
    (net (code "104") (name "GPIO10") (class "Default")
      (node (ref "CN3") (pin "8") (pinfunction "8_8") (pintype "unspecified"))
      (node (ref "U6") (pin "12") (pinfunction "12_12") (pintype "unspecified"))
    )
    (net (code "105") (name "GPIO11") (class "Default")
      (node (ref "CN3") (pin "7") (pinfunction "7_7") (pintype "unspecified"))
      (node (ref "U5") (pin "12") (pinfunction "12_12") (pintype "unspecified"))
    )
    (net (code "106") (name "GPIO12") (class "Default")
      (node (ref "R59") (pin "2") (pinfunction "2_2") (pintype "input"))
      (node (ref "U6") (pin "11") (pinfunction "11_11") (pintype "unspecified"))
    )
    (net (code "107") (name "GPIO13") (class "Default")
      (node (ref "R63") (pin "2") (pinfunction "2_2") (pintype "input"))
      (node (ref "U5") (pin "11") (pinfunction "11_11") (pintype "unspecified"))
    )
    (net (code "108") (name "GPIO14") (class "Default")
      (node (ref "R65") (pin "2") (pinfunction "2_2") (pintype "input"))
      (node (ref "U6") (pin "10") (pinfunction "10_10") (pintype "unspecified"))
    )
    (net (code "109") (name "GPIO32") (class "Default")
      (node (ref "U30") (pin "4") (pinfunction "SDA_4") (pintype "unspecified"))
      (node (ref "U8") (pin "6") (pinfunction "6_6") (pintype "unspecified"))
    )
    (net (code "110") (name "GPIO33") (class "Default")
      (node (ref "U30") (pin "3") (pinfunction "SCL_3") (pintype "unspecified"))
      (node (ref "U7") (pin "6") (pinfunction "6_6") (pintype "unspecified"))
    )
    (net (code "111") (name "GPIO48") (class "Default")
      (node (ref "SW1") (pin "3") (pinfunction "3_3") (pintype "unspecified"))
      (node (ref "SW4") (pin "3") (pinfunction "3_3") (pintype "unspecified"))
      (node (ref "SW7") (pin "3") (pinfunction "3_3") (pintype "unspecified"))
      (node (ref "U8") (pin "7") (pinfunction "7_7") (pintype "unspecified"))
    )
    (net (code "112") (name "GPIO49") (class "Default")
      (node (ref "SW2") (pin "3") (pinfunction "3_3") (pintype "unspecified"))
      (node (ref "SW5") (pin "3") (pinfunction "3_3") (pintype "unspecified"))
      (node (ref "SW8") (pin "3") (pinfunction "3_3") (pintype "unspecified"))
      (node (ref "U7") (pin "7") (pinfunction "7_7") (pintype "unspecified"))
    )
    (net (code "113") (name "GPIO50") (class "Default")
      (node (ref "SW3") (pin "3") (pinfunction "3_3") (pintype "unspecified"))
      (node (ref "SW6") (pin "3") (pinfunction "3_3") (pintype "unspecified"))
      (node (ref "SW9") (pin "3") (pinfunction "3_3") (pintype "unspecified"))
      (node (ref "U8") (pin "8") (pinfunction "8_8") (pintype "unspecified"))
    )
    (net (code "114") (name "GPIO64") (class "Default")
      (node (ref "R58") (pin "2") (pinfunction "2_2") (pintype "input"))
      (node (ref "U8") (pin "15") (pinfunction "15_15") (pintype "unspecified"))
    )
    (net (code "115") (name "GPIO65") (class "Default")
      (node (ref "R57") (pin "2") (pinfunction "2_2") (pintype "input"))
      (node (ref "U7") (pin "15") (pinfunction "15_15") (pintype "unspecified"))
    )
    (net (code "116") (name "GPIO66") (class "Default")
      (node (ref "R56") (pin "2") (pinfunction "2_2") (pintype "input"))
      (node (ref "U8") (pin "16") (pinfunction "16_16") (pintype "unspecified"))
    )
    (net (code "117") (name "GPIO67") (class "Default")
      (node (ref "R55") (pin "2") (pinfunction "2_2") (pintype "input"))
      (node (ref "U7") (pin "16") (pinfunction "16_16") (pintype "unspecified"))
    )
    (net (code "118") (name "GPIO68") (class "Default")
      (node (ref "R54") (pin "2") (pinfunction "2_2") (pintype "input"))
      (node (ref "U8") (pin "17") (pinfunction "17_17") (pintype "unspecified"))
    )
    (net (code "119") (name "Net-(D3-K)") (class "Default")
      (node (ref "C68") (pin "2") (pinfunction "2_2") (pintype "unspecified"))
      (node (ref "D3") (pin "1") (pinfunction "K_1") (pintype "unspecified"))
      (node (ref "L3") (pin "1") (pinfunction "1_1") (pintype "input"))
      (node (ref "U18") (pin "8") (pinfunction "PH_8") (pintype "unspecified"))
    )
    (net (code "120") (name "Net-(DC1-Pad1)") (class "Default")
      (node (ref "DC1") (pin "1") (pinfunction "1_1") (pintype "unspecified"))
      (node (ref "SW12") (pin "2") (pinfunction "2_2") (pintype "unspecified"))
    )
    (net (code "121") (name "Net-(LED6-+)") (class "Default")
      (node (ref "LED6") (pin "1") (pinfunction "+_1") (pintype "unspecified"))
      (node (ref "R54") (pin "1") (pinfunction "1_1") (pintype "input"))
    )
    (net (code "122") (name "Net-(LED7-+)") (class "Default")
      (node (ref "LED7") (pin "1") (pinfunction "+_1") (pintype "unspecified"))
      (node (ref "R55") (pin "1") (pinfunction "1_1") (pintype "input"))
    )
    (net (code "123") (name "Net-(LED8-+)") (class "Default")
      (node (ref "LED8") (pin "1") (pinfunction "+_1") (pintype "unspecified"))
      (node (ref "R56") (pin "1") (pinfunction "1_1") (pintype "input"))
    )
    (net (code "124") (name "Net-(LED9-+)") (class "Default")
      (node (ref "LED9") (pin "1") (pinfunction "+_1") (pintype "unspecified"))
      (node (ref "R57") (pin "1") (pinfunction "1_1") (pintype "input"))
    )
    (net (code "125") (name "Net-(LED10-+)") (class "Default")
      (node (ref "LED10") (pin "1") (pinfunction "+_1") (pintype "unspecified"))
      (node (ref "R58") (pin "1") (pinfunction "1_1") (pintype "input"))
    )
    (net (code "126") (name "Net-(LED11-+)") (class "Default")
      (node (ref "LED11") (pin "1") (pinfunction "+_1") (pintype "unspecified"))
      (node (ref "R82") (pin "1") (pinfunction "1_1") (pintype "input"))
    )
    (net (code "127") (name "Net-(R59-Pad1)") (class "Default")
      (node (ref "R59") (pin "1") (pinfunction "1_1") (pintype "input"))
      (node (ref "R61") (pin "1") (pinfunction "1_1") (pintype "input"))
      (node (ref "SW1") (pin "2") (pinfunction "2_2") (pintype "unspecified"))
      (node (ref "SW2") (pin "2") (pinfunction "2_2") (pintype "unspecified"))
      (node (ref "SW3") (pin "2") (pinfunction "2_2") (pintype "unspecified"))
    )
    (net (code "128") (name "Net-(R62-Pad1)") (class "Default")
      (node (ref "R62") (pin "1") (pinfunction "1_1") (pintype "input"))
      (node (ref "R63") (pin "1") (pinfunction "1_1") (pintype "input"))
      (node (ref "SW4") (pin "2") (pinfunction "2_2") (pintype "unspecified"))
      (node (ref "SW5") (pin "2") (pinfunction "2_2") (pintype "unspecified"))
      (node (ref "SW6") (pin "2") (pinfunction "2_2") (pintype "unspecified"))
    )
    (net (code "129") (name "Net-(R64-Pad1)") (class "Default")
      (node (ref "R64") (pin "1") (pinfunction "1_1") (pintype "input"))
      (node (ref "R65") (pin "1") (pinfunction "1_1") (pintype "input"))
      (node (ref "SW7") (pin "2") (pinfunction "2_2") (pintype "unspecified"))
      (node (ref "SW8") (pin "2") (pinfunction "2_2") (pintype "unspecified"))
      (node (ref "SW9") (pin "2") (pinfunction "2_2") (pintype "unspecified"))
    )
    (net (code "130") (name "Net-(U1-+IN)") (class "Default")
      (node (ref "C80") (pin "2") (pinfunction "2_2") (pintype "input"))
      (node (ref "R3") (pin "1") (pinfunction "1_1") (pintype "unspecified"))
      (node (ref "R4") (pin "2") (pinfunction "2_2") (pintype "unspecified"))
      (node (ref "U1") (pin "3") (pinfunction "+IN_3") (pintype "unspecified"))
    )
    (net (code "131") (name "Net-(U1--IN)") (class "Default")
      (node (ref "C94") (pin "2") (pinfunction "2_2") (pintype "input"))
      (node (ref "R2") (pin "1") (pinfunction "1_1") (pintype "unspecified"))
      (node (ref "R81") (pin "1") (pinfunction "1_1") (pintype "unspecified"))
      (node (ref "U1") (pin "4") (pinfunction "-IN_4") (pintype "unspecified"))
    )
    (net (code "132") (name "Net-(U1-OUT)") (class "Default")
      (node (ref "C94") (pin "1") (pinfunction "1_1") (pintype "input"))
      (node (ref "R5") (pin "2") (pinfunction "2_2") (pintype "unspecified"))
      (node (ref "R81") (pin "2") (pinfunction "2_2") (pintype "unspecified"))
      (node (ref "U1") (pin "1") (pinfunction "OUT_1") (pintype "output"))
    )
    (net (code "133") (name "Net-(U1-V+)") (class "Default")
      (node (ref "FB2") (pin "2") (pinfunction "2_2") (pintype "unspecified"))
      (node (ref "U1") (pin "5") (pinfunction "V+_5") (pintype "unspecified"))
    )
    (net (code "134") (name "Net-(U2-VOUTN)") (class "Default")
      (node (ref "C79") (pin "2") (pinfunction "2_2") (pintype "input"))
      (node (ref "R2") (pin "2") (pinfunction "2_2") (pintype "unspecified"))
      (node (ref "U2") (pin "6") (pinfunction "VOUTN_6") (pintype "unspecified"))
    )
    (net (code "135") (name "Net-(U2-VOUTP)") (class "Default")
      (node (ref "C79") (pin "1") (pinfunction "1_1") (pintype "input"))
      (node (ref "R3") (pin "2") (pinfunction "2_2") (pintype "unspecified"))
      (node (ref "U2") (pin "7") (pinfunction "VOUTP_7") (pintype "unspecified"))
    )
    (net (code "136") (name "Net-(U18-BOOT)") (class "Default")
      (node (ref "C68") (pin "1") (pinfunction "1_1") (pintype "unspecified"))
      (node (ref "U18") (pin "1") (pinfunction "BOOT_1") (pintype "unspecified"))
    )
    (net (code "137") (name "Net-(U18-VSENSE)") (class "Default")
      (node (ref "R66") (pin "2") (pinfunction "2_2") (pintype "unspecified"))
      (node (ref "R67") (pin "1") (pinfunction "1_1") (pintype "input"))
      (node (ref "U18") (pin "4") (pinfunction "VSENSE_4") (pintype "unspecified"))
    )
    (net (code "138") (name "Net-(U21-+IN)") (class "Default")
      (node (ref "C89") (pin "2") (pinfunction "2_2") (pintype "input"))
      (node (ref "R69") (pin "1") (pinfunction "1_1") (pintype "unspecified"))
      (node (ref "R70") (pin "2") (pinfunction "2_2") (pintype "unspecified"))
      (node (ref "U21") (pin "3") (pinfunction "+IN_3") (pintype "unspecified"))
    )
    (net (code "139") (name "Net-(U21--IN)") (class "Default")
      (node (ref "C95") (pin "2") (pinfunction "2_2") (pintype "input"))
      (node (ref "R68") (pin "1") (pinfunction "1_1") (pintype "unspecified"))
      (node (ref "R80") (pin "1") (pinfunction "1_1") (pintype "unspecified"))
      (node (ref "U21") (pin "4") (pinfunction "-IN_4") (pintype "unspecified"))
    )
    (net (code "140") (name "Net-(U21-OUT)") (class "Default")
      (node (ref "C95") (pin "1") (pinfunction "1_1") (pintype "input"))
      (node (ref "R72") (pin "2") (pinfunction "2_2") (pintype "unspecified"))
      (node (ref "R80") (pin "2") (pinfunction "2_2") (pintype "unspecified"))
      (node (ref "U21") (pin "1") (pinfunction "OUT_1") (pintype "output"))
    )
    (net (code "141") (name "Net-(U21-V+)") (class "Default")
      (node (ref "FB3") (pin "2") (pinfunction "2_2") (pintype "unspecified"))
      (node (ref "U21") (pin "5") (pinfunction "V+_5") (pintype "unspecified"))
    )
    (net (code "142") (name "Net-(U22-VOUTN)") (class "Default")
      (node (ref "C88") (pin "2") (pinfunction "2_2") (pintype "input"))
      (node (ref "R68") (pin "2") (pinfunction "2_2") (pintype "unspecified"))
      (node (ref "U22") (pin "6") (pinfunction "VOUTN_6") (pintype "unspecified"))
    )
    (net (code "143") (name "Net-(U22-VOUTP)") (class "Default")
      (node (ref "C88") (pin "1") (pinfunction "1_1") (pintype "input"))
      (node (ref "R69") (pin "2") (pinfunction "2_2") (pintype "unspecified"))
      (node (ref "U22") (pin "7") (pinfunction "VOUTP_7") (pintype "unspecified"))
    )
    (net (code "144") (name "VAA200") (class "Default")
      (node (ref "C78") (pin "2") (pinfunction "2_2") (pintype "input"))
      (node (ref "U2") (pin "2") (pinfunction "VIN_2") (pintype "unspecified"))
      (node (ref "U45") (pin "1") (pinfunction "1_1") (pintype "unspecified"))
    )
    (net (code "145") (name "VAA400") (class "Default")
      (node (ref "C87") (pin "2") (pinfunction "2_2") (pintype "input"))
      (node (ref "U22") (pin "2") (pinfunction "VIN_2") (pintype "unspecified"))
      (node (ref "U44") (pin "1") (pinfunction "1_1") (pintype "unspecified"))
    )
    (net (code "146") (name "unconnected-(SCREW1-Pad1)") (class "Default")
      (node (ref "SCREW1") (pin "1") (pinfunction "1_1") (pintype "input"))
    )
    (net (code "147") (name "unconnected-(SCREW2-Pad1)") (class "Default")
      (node (ref "SCREW2") (pin "1") (pinfunction "1_1") (pintype "input"))
    )
    (net (code "148") (name "unconnected-(SCREW3-Pad1)") (class "Default")
      (node (ref "SCREW3") (pin "1") (pinfunction "1_1") (pintype "input"))
    )
    (net (code "149") (name "unconnected-(SCREW4-Pad1)") (class "Default")
      (node (ref "SCREW4") (pin "1") (pinfunction "1_1") (pintype "input"))
    )
    (net (code "150") (name "unconnected-(SW1-Pad1)") (class "Default")
      (node (ref "SW1") (pin "1") (pinfunction "1_1") (pintype "unspecified"))
    )
    (net (code "151") (name "unconnected-(SW1-Pad4)") (class "Default")
      (node (ref "SW1") (pin "4") (pinfunction "4_4") (pintype "unspecified"))
    )
    (net (code "152") (name "unconnected-(SW2-Pad1)") (class "Default")
      (node (ref "SW2") (pin "1") (pinfunction "1_1") (pintype "unspecified"))
    )
    (net (code "153") (name "unconnected-(SW2-Pad4)") (class "Default")
      (node (ref "SW2") (pin "4") (pinfunction "4_4") (pintype "unspecified"))
    )
    (net (code "154") (name "unconnected-(SW3-Pad1)") (class "Default")
      (node (ref "SW3") (pin "1") (pinfunction "1_1") (pintype "unspecified"))
    )
    (net (code "155") (name "unconnected-(SW3-Pad4)") (class "Default")
      (node (ref "SW3") (pin "4") (pinfunction "4_4") (pintype "unspecified"))
    )
    (net (code "156") (name "unconnected-(SW4-Pad1)") (class "Default")
      (node (ref "SW4") (pin "1") (pinfunction "1_1") (pintype "unspecified"))
    )
    (net (code "157") (name "unconnected-(SW4-Pad4)") (class "Default")
      (node (ref "SW4") (pin "4") (pinfunction "4_4") (pintype "unspecified"))
    )
    (net (code "158") (name "unconnected-(SW5-Pad1)") (class "Default")
      (node (ref "SW5") (pin "1") (pinfunction "1_1") (pintype "unspecified"))
    )
    (net (code "159") (name "unconnected-(SW5-Pad4)") (class "Default")
      (node (ref "SW5") (pin "4") (pinfunction "4_4") (pintype "unspecified"))
    )
    (net (code "160") (name "unconnected-(SW6-Pad1)") (class "Default")
      (node (ref "SW6") (pin "1") (pinfunction "1_1") (pintype "unspecified"))
    )
    (net (code "161") (name "unconnected-(SW6-Pad4)") (class "Default")
      (node (ref "SW6") (pin "4") (pinfunction "4_4") (pintype "unspecified"))
    )
    (net (code "162") (name "unconnected-(SW7-Pad1)") (class "Default")
      (node (ref "SW7") (pin "1") (pinfunction "1_1") (pintype "unspecified"))
    )
    (net (code "163") (name "unconnected-(SW7-Pad4)") (class "Default")
      (node (ref "SW7") (pin "4") (pinfunction "4_4") (pintype "unspecified"))
    )
    (net (code "164") (name "unconnected-(SW8-Pad1)") (class "Default")
      (node (ref "SW8") (pin "1") (pinfunction "1_1") (pintype "unspecified"))
    )
    (net (code "165") (name "unconnected-(SW8-Pad4)") (class "Default")
      (node (ref "SW8") (pin "4") (pinfunction "4_4") (pintype "unspecified"))
    )
    (net (code "166") (name "unconnected-(SW9-Pad1)") (class "Default")
      (node (ref "SW9") (pin "1") (pinfunction "1_1") (pintype "unspecified"))
    )
    (net (code "167") (name "unconnected-(SW9-Pad4)") (class "Default")
      (node (ref "SW9") (pin "4") (pinfunction "4_4") (pintype "unspecified"))
    )
    (net (code "168") (name "unconnected-(SW12-Pad3)") (class "Default")
      (node (ref "SW12") (pin "3") (pinfunction "3_3") (pintype "unspecified"))
    )
    (net (code "169") (name "unconnected-(SW12-Pad4)") (class "Default")
      (node (ref "SW12") (pin "4") (pinfunction "4_4") (pintype "unspecified"))
    )
    (net (code "170") (name "unconnected-(SW12-Pad5)") (class "Default")
      (node (ref "SW12") (pin "5") (pinfunction "5_5") (pintype "unspecified"))
    )
    (net (code "171") (name "unconnected-(SW12-Pad6)") (class "Default")
      (node (ref "SW12") (pin "6") (pinfunction "6_6") (pintype "unspecified"))
    )
    (net (code "172") (name "unconnected-(U9-Pad2)") (class "Default")
      (node (ref "U9") (pin "2") (pinfunction "2_2") (pintype "unspecified"))
    )
    (net (code "173") (name "unconnected-(U10-Pad2)") (class "Default")
      (node (ref "U10") (pin "2") (pinfunction "2_2") (pintype "unspecified"))
    )
    (net (code "174") (name "unconnected-(U18-ENA-Pad5)") (class "Default")
      (node (ref "U18") (pin "5") (pinfunction "ENA_5") (pintype "unspecified+no_connect"))
    )
    (net (code "175") (name "unconnected-(U18-NC-Pad2)") (class "Default")
      (node (ref "U18") (pin "2") (pinfunction "NC_2") (pintype "unspecified+no_connect"))
    )
    (net (code "176") (name "unconnected-(U18-NC-Pad3)") (class "Default")
      (node (ref "U18") (pin "3") (pinfunction "NC_3") (pintype "unspecified+no_connect"))
    )
  )
)
